# F103ZET6.net
KiCad netlist of a schematic drawn in Altium Designer
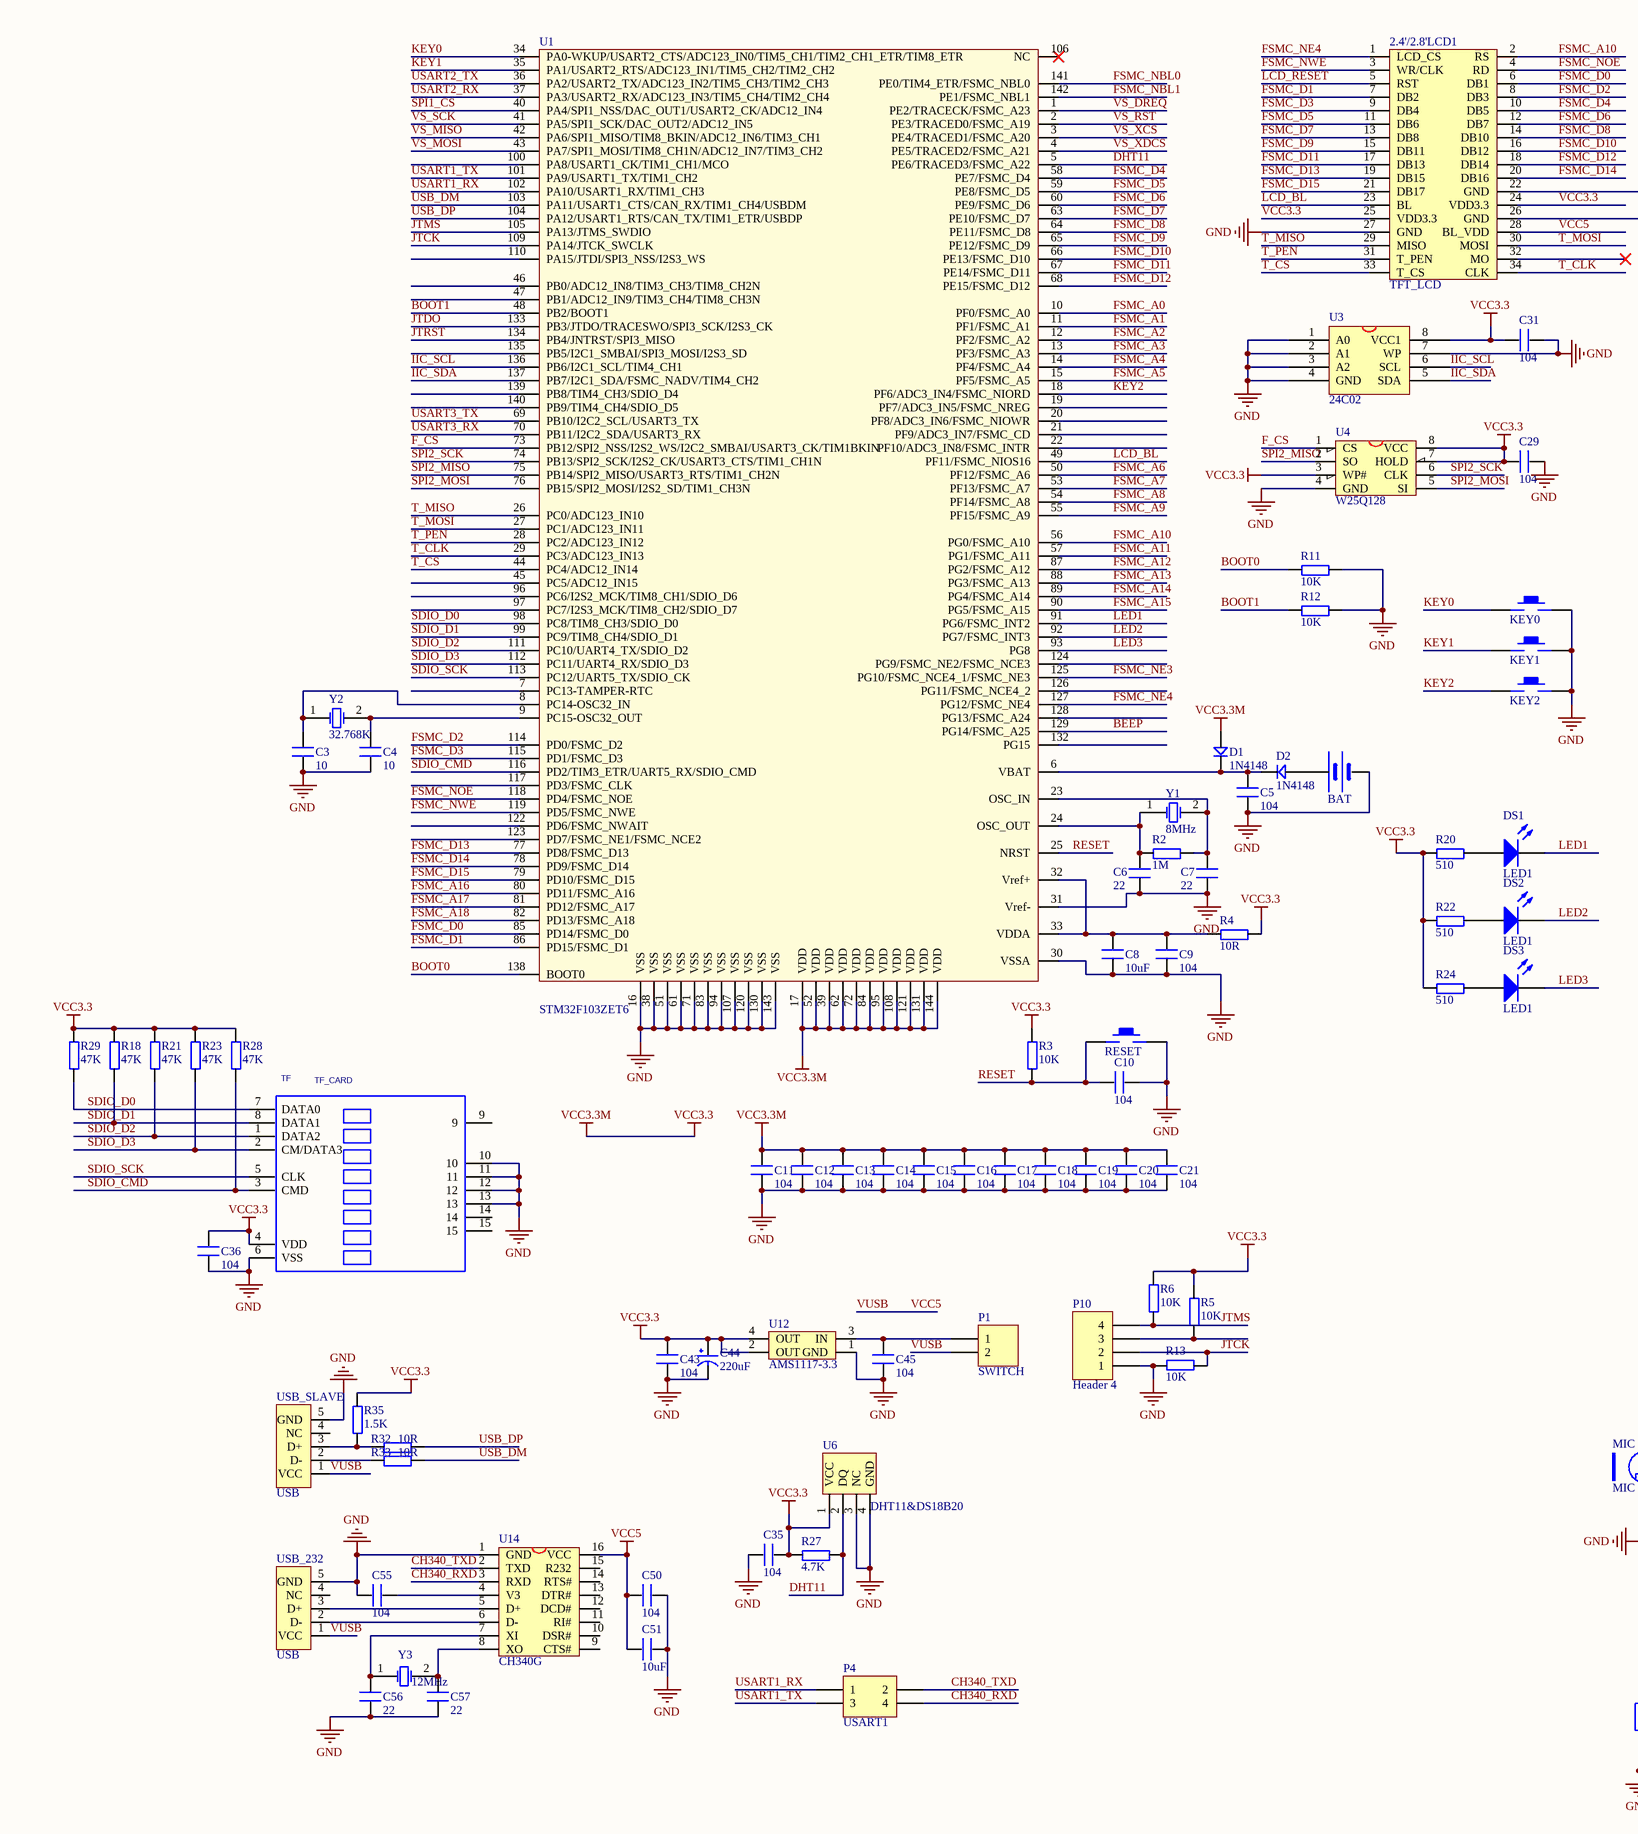
[diagram p0: F103ZET6.SchDoc, left]
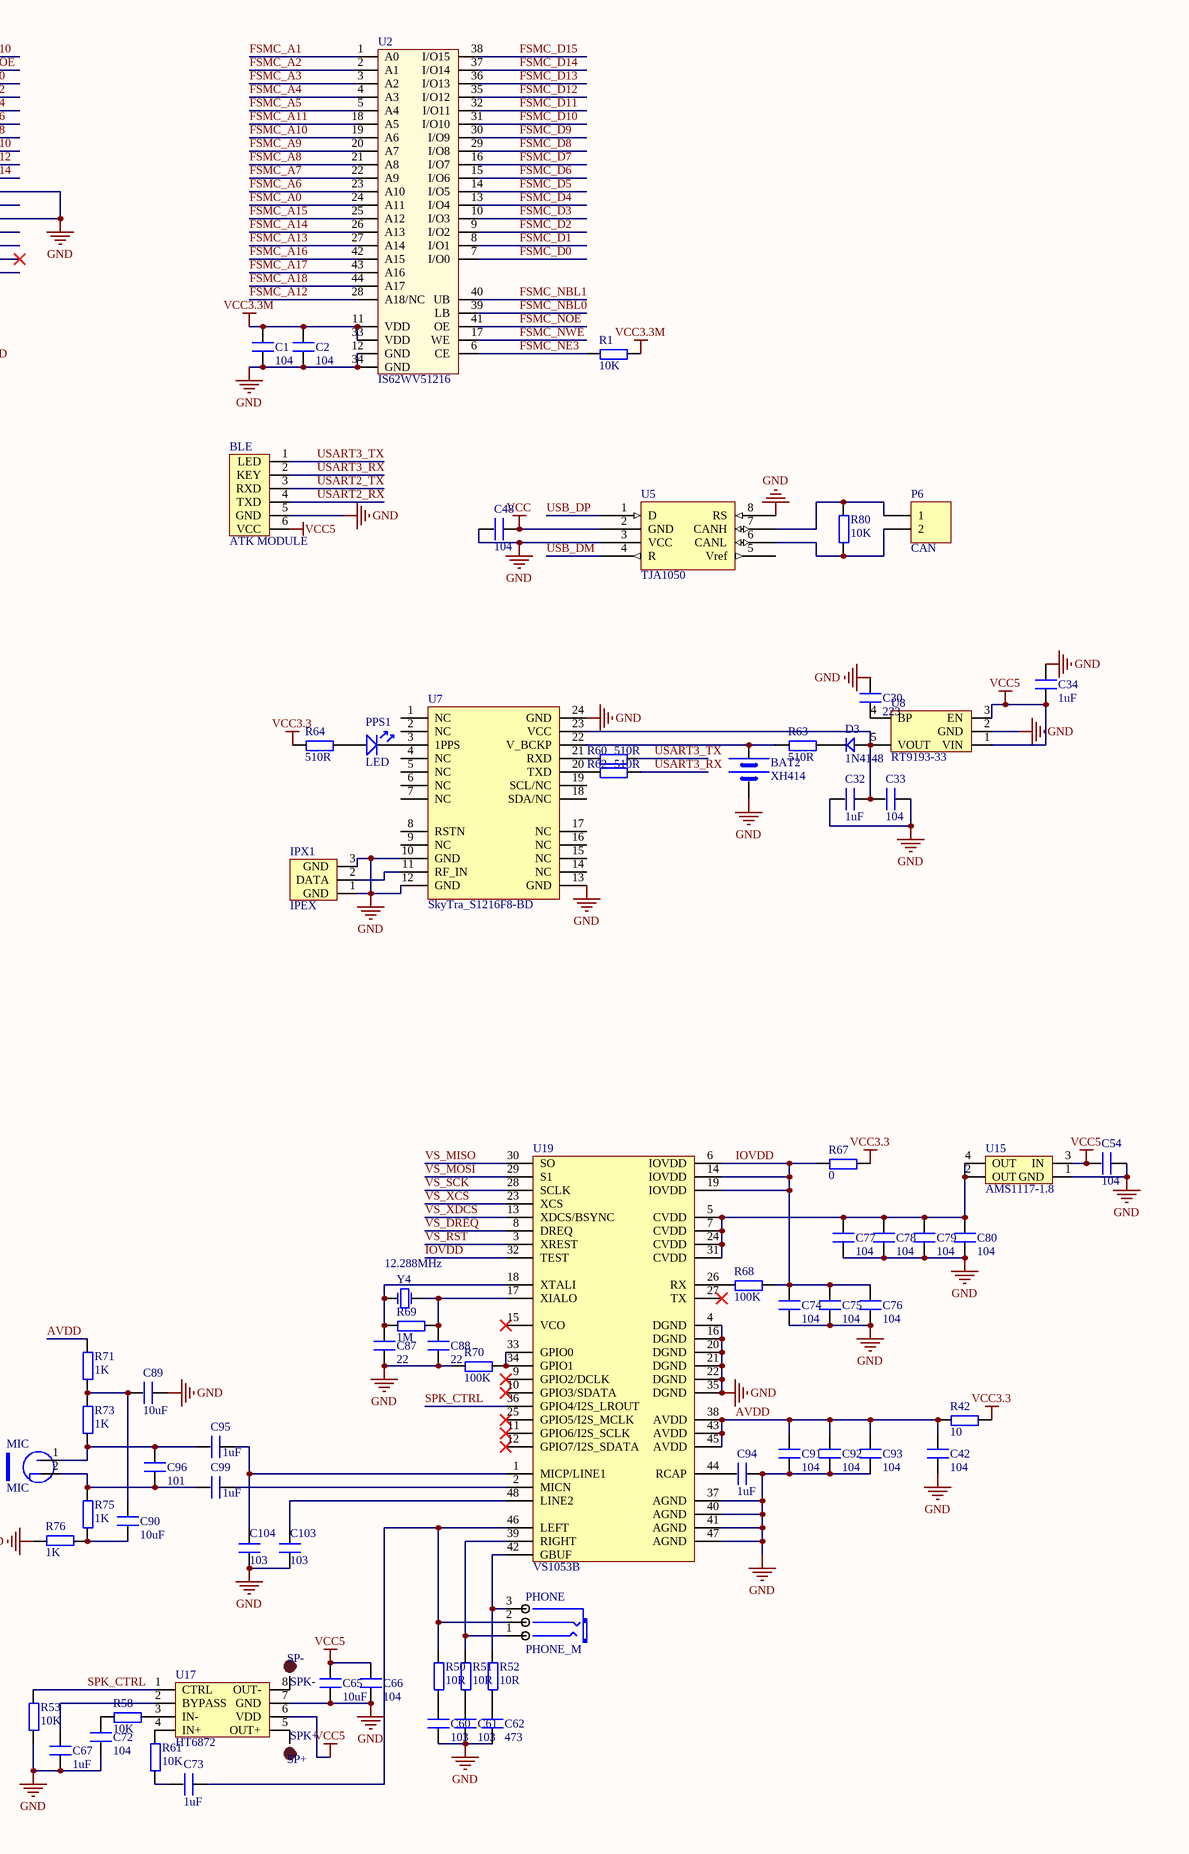
[diagram p1: F103ZET6.SchDoc, right]

(export (version "E")
  (design (tool "Eeschema 10.0.6"))
  (components
    (comp (ref "2.4'/2.8'LCD1")
      (value "TFT_LCD")
      (footprint "db2*17-4.3")
      (libsource (lib "WarShip V3 STM32103封装库") (part "TFT_LCD"))
    )
    (comp (ref "BAT")
      (value "BATT")
      (footprint "CR1220_A")
      (libsource (lib "WarShip V3 STM32103封装库") (part "BAT"))
    )
    (comp (ref "BAT2")
      (value "XH414")
      (footprint "XH414")
      (description "XH414 IV01E")
      (libsource (lib "ATK_S1216F8_BD_V1.1") (part "XH414"))
    )
    (comp (ref "BLE")
      (value "ATK MODULE")
      (footprint "HEAD6")
      (description "ATK-HC05")
      (libsource (lib "WarShip V3 STM32103封装库") (part "ATK-HC05"))
    )
    (comp (ref "C1")
      (value "104")
      (footprint "C 0603_M")
      (libsource (lib "WarShip V3 STM32103封装库") (part "C"))
    )
    (comp (ref "C2")
      (value "104")
      (footprint "C 0603_M")
      (libsource (lib "WarShip V3 STM32103封装库") (part "C"))
    )
    (comp (ref "C3")
      (value "10")
      (footprint "C 0603_M")
      (libsource (lib "WarShip V3 STM32103封装库") (part "C"))
    )
    (comp (ref "C4")
      (value "10")
      (footprint "C 0603_M")
      (libsource (lib "WarShip V3 STM32103封装库") (part "C"))
    )
    (comp (ref "C5")
      (value "104")
      (footprint "C 0603_M")
      (libsource (lib "WarShip V3 STM32103封装库") (part "C"))
    )
    (comp (ref "C6")
      (value "22")
      (footprint "C 0603_M")
      (libsource (lib "WarShip V3 STM32103封装库") (part "C"))
    )
    (comp (ref "C7")
      (value "22")
      (footprint "C 0603_M")
      (libsource (lib "WarShip V3 STM32103封装库") (part "C"))
    )
    (comp (ref "C8")
      (value "10uF")
      (footprint "C 0805_M")
      (libsource (lib "WarShip V3 STM32103封装库") (part "C"))
    )
    (comp (ref "C9")
      (value "104")
      (footprint "C 0603_M")
      (libsource (lib "WarShip V3 STM32103封装库") (part "C"))
    )
    (comp (ref "C10")
      (value "104")
      (footprint "C 0603_M")
      (libsource (lib "WarShip V3 STM32103封装库") (part "C"))
    )
    (comp (ref "C11")
      (value "104")
      (footprint "C 0603_M")
      (libsource (lib "WarShip V3 STM32103封装库") (part "C"))
    )
    (comp (ref "C12")
      (value "104")
      (footprint "C 0603_M")
      (libsource (lib "WarShip V3 STM32103封装库") (part "C"))
    )
    (comp (ref "C13")
      (value "104")
      (footprint "C 0603_M")
      (libsource (lib "WarShip V3 STM32103封装库") (part "C"))
    )
    (comp (ref "C14")
      (value "104")
      (footprint "C 0603_M")
      (libsource (lib "WarShip V3 STM32103封装库") (part "C"))
    )
    (comp (ref "C15")
      (value "104")
      (footprint "C 0603_M")
      (libsource (lib "WarShip V3 STM32103封装库") (part "C"))
    )
    (comp (ref "C16")
      (value "104")
      (footprint "C 0603_M")
      (libsource (lib "WarShip V3 STM32103封装库") (part "C"))
    )
    (comp (ref "C17")
      (value "104")
      (footprint "C 0603_M")
      (libsource (lib "WarShip V3 STM32103封装库") (part "C"))
    )
    (comp (ref "C18")
      (value "104")
      (footprint "C 0603_M")
      (libsource (lib "WarShip V3 STM32103封装库") (part "C"))
    )
    (comp (ref "C19")
      (value "104")
      (footprint "C 0603_M")
      (libsource (lib "WarShip V3 STM32103封装库") (part "C"))
    )
    (comp (ref "C20")
      (value "104")
      (footprint "C 0603_M")
      (libsource (lib "WarShip V3 STM32103封装库") (part "C"))
    )
    (comp (ref "C21")
      (value "104")
      (footprint "C 0603_M")
      (libsource (lib "WarShip V3 STM32103封装库") (part "C"))
    )
    (comp (ref "C29")
      (value "104")
      (footprint "C 0603_M")
      (libsource (lib "WarShip V3 STM32103封装库") (part "C"))
    )
    (comp (ref "C30") (value "223") (footprint "0603P") (libsource (lib "ATK_S1216F8_BD_V1.1") (part "C")))
    (comp (ref "C31")
      (value "104")
      (footprint "C 0603_M")
      (libsource (lib "WarShip V3 STM32103封装库") (part "C"))
    )
    (comp (ref "C32") (value "1uF") (footprint "0603P") (libsource (lib "ATK_S1216F8_BD_V1.1") (part "C")))
    (comp (ref "C33") (value "104") (footprint "0603P") (libsource (lib "ATK_S1216F8_BD_V1.1") (part "C")))
    (comp (ref "C34") (value "1uF") (footprint "0603P") (libsource (lib "ATK_S1216F8_BD_V1.1") (part "C")))
    (comp (ref "C35")
      (value "104")
      (footprint "C 0603_M")
      (libsource (lib "WarShip V3 STM32103封装库") (part "C"))
    )
    (comp (ref "C36")
      (value "104")
      (footprint "C 0603_M")
      (libsource (lib "WarShip V3 STM32103封装库") (part "C"))
    )
    (comp (ref "C42") (value "104") (footprint "C 0603_M") (libsource (lib "ATK-VS1053 MP3") (part "C")))
    (comp (ref "C43")
      (value "104")
      (footprint "C 0603_M")
      (libsource (lib "WarShip V3 STM32103封装库") (part "C"))
    )
    (comp (ref "C44")
      (value "220uF")
      (footprint "CT 6*6 - C")
      (libsource (lib "WarShip V3 STM32103封装库") (part "CAP"))
    )
    (comp (ref "C45")
      (value "104")
      (footprint "C 0603_M")
      (libsource (lib "WarShip V3 STM32103封装库") (part "C"))
    )
    (comp (ref "C48") (value "104") (footprint "0603P") (libsource (lib "WarShip V3 STM32103封装库") (part "C")))
    (comp (ref "C50")
      (value "104")
      (footprint "C 0603_M")
      (libsource (lib "WarShip V3 STM32103封装库") (part "C"))
    )
    (comp (ref "C51")
      (value "10uF")
      (footprint "C 0805_M")
      (libsource (lib "WarShip V3 STM32103封装库") (part "C"))
    )
    (comp (ref "C54") (value "104") (footprint "C 0603_M") (libsource (lib "ATK-VS1053 MP3") (part "C")))
    (comp (ref "C55")
      (value "104")
      (footprint "C 0603_M")
      (libsource (lib "WarShip V3 STM32103封装库") (part "C"))
    )
    (comp (ref "C56")
      (value "22")
      (footprint "C 0603_M")
      (libsource (lib "WarShip V3 STM32103封装库") (part "C"))
    )
    (comp (ref "C57")
      (value "22")
      (footprint "C 0603_M")
      (libsource (lib "WarShip V3 STM32103封装库") (part "C"))
    )
    (comp (ref "C60")
      (value "103")
      (footprint "C 0603_M")
      (libsource (lib "WarShip V3 STM32103封装库") (part "C"))
    )
    (comp (ref "C61")
      (value "103")
      (footprint "C 0603_M")
      (libsource (lib "WarShip V3 STM32103封装库") (part "C"))
    )
    (comp (ref "C62")
      (value "473")
      (footprint "C 0603_M")
      (libsource (lib "WarShip V3 STM32103封装库") (part "C"))
    )
    (comp (ref "C65")
      (value "10uF")
      (footprint "C 0805_M")
      (libsource (lib "WarShip V3 STM32103封装库") (part "C"))
    )
    (comp (ref "C66")
      (value "104")
      (footprint "C 0603_M")
      (libsource (lib "WarShip V3 STM32103封装库") (part "C"))
    )
    (comp (ref "C67")
      (value "1uF")
      (footprint "C 0603_M")
      (libsource (lib "WarShip V3 STM32103封装库") (part "C"))
    )
    (comp (ref "C72")
      (value "104")
      (footprint "C 0603_M")
      (libsource (lib "WarShip V3 STM32103封装库") (part "C"))
    )
    (comp (ref "C73")
      (value "1uF")
      (footprint "C 0603_M")
      (libsource (lib "WarShip V3 STM32103封装库") (part "C"))
    )
    (comp (ref "C74") (value "104") (footprint "C 0603_M") (libsource (lib "ATK-VS1053 MP3") (part "C")))
    (comp (ref "C75") (value "104") (footprint "C 0603_M") (libsource (lib "ATK-VS1053 MP3") (part "C")))
    (comp (ref "C76") (value "104") (footprint "C 0603_M") (libsource (lib "ATK-VS1053 MP3") (part "C")))
    (comp (ref "C77") (value "104") (footprint "C 0603_M") (libsource (lib "ATK-VS1053 MP3") (part "C")))
    (comp (ref "C78") (value "104") (footprint "C 0603_M") (libsource (lib "ATK-VS1053 MP3") (part "C")))
    (comp (ref "C79") (value "104") (footprint "C 0603_M") (libsource (lib "ATK-VS1053 MP3") (part "C")))
    (comp (ref "C80") (value "104") (footprint "C 0603_M") (libsource (lib "ATK-VS1053 MP3") (part "C")))
    (comp (ref "C87") (value "22") (footprint "C 0603_M") (libsource (lib "ATK-VS1053 MP3") (part "C")))
    (comp (ref "C88") (value "22") (footprint "C 0603_M") (libsource (lib "ATK-VS1053 MP3") (part "C")))
    (comp (ref "C89")
      (value "10uF")
      (footprint "C 0805_M")
      (libsource (lib "WarShip V3 STM32103封装库") (part "C"))
    )
    (comp (ref "C90")
      (value "10uF")
      (footprint "C 0805_M")
      (libsource (lib "WarShip V3 STM32103封装库") (part "C"))
    )
    (comp (ref "C91") (value "104") (footprint "C 0603_M") (libsource (lib "ATK-VS1053 MP3") (part "C")))
    (comp (ref "C92") (value "104") (footprint "C 0603_M") (libsource (lib "ATK-VS1053 MP3") (part "C")))
    (comp (ref "C93") (value "104") (footprint "C 0603_M") (libsource (lib "ATK-VS1053 MP3") (part "C")))
    (comp (ref "C94") (value "1uF") (footprint "C 0603_M") (libsource (lib "ATK-VS1053 MP3") (part "C")))
    (comp (ref "C95")
      (value "1uF")
      (footprint "C 0603_M")
      (libsource (lib "WarShip V3 STM32103封装库") (part "C"))
    )
    (comp (ref "C96")
      (value "101")
      (footprint "C 0603_M")
      (libsource (lib "WarShip V3 STM32103封装库") (part "C"))
    )
    (comp (ref "C99")
      (value "1uF")
      (footprint "C 0603_M")
      (libsource (lib "WarShip V3 STM32103封装库") (part "C"))
    )
    (comp (ref "C103")
      (value "103")
      (footprint "C 0603_M")
      (libsource (lib "WarShip V3 STM32103封装库") (part "C"))
    )
    (comp (ref "C104")
      (value "103")
      (footprint "C 0603_M")
      (libsource (lib "WarShip V3 STM32103封装库") (part "C"))
    )
    (comp (ref "D1")
      (value "1N4148")
      (footprint "DIODE_SOP")
      (libsource (lib "WarShip V3 STM32103封装库") (part "D"))
    )
    (comp (ref "D2")
      (value "1N4148")
      (footprint "DIODE_SOP")
      (libsource (lib "WarShip V3 STM32103封装库") (part "D"))
    )
    (comp (ref "D3")
      (value "1N4148")
      (footprint "DIODE_SOP")
      (libsource (lib "ATK_S1216F8_BD_V1.1") (part "D"))
    )
    (comp (ref "DS1")
      (value "LED1")
      (footprint "LED 0603R")
      (description "Typical RED, GREEN, YELLOW, AMBER GaAs LED")
      (fields (field (name "PUBLISHER") "Altium Limited"))
      (libsource (lib "WarShip V3 STM32103封装库") (part "LED2"))
    )
    (comp (ref "DS2")
      (value "LED1")
      (footprint "LED 0603R")
      (description "Typical RED, GREEN, YELLOW, AMBER GaAs LED")
      (fields (field (name "PUBLISHER") "Altium Limited"))
      (libsource (lib "WarShip V3 STM32103封装库") (part "LED2"))
    )
    (comp (ref "DS3")
      (value "LED1")
      (footprint "LED 0603R")
      (description "Typical RED, GREEN, YELLOW, AMBER GaAs LED")
      (fields (field (name "PUBLISHER") "Altium Limited"))
      (libsource (lib "WarShip V3 STM32103封装库") (part "LED2"))
    )
    (comp (ref "IPX1")
      (value "IPEX")
      (footprint "IPEX")
      (description "IPEX座")
      (libsource (lib "ATK_S1216F8_BD_V1.1") (part "IPEX"))
    )
    (comp (ref "KEY0")
      (value "KEY_M")
      (footprint "TSW SMD-3*6*2.5")
      (libsource (lib "WarShip V3 STM32103封装库") (part "KEY_M"))
    )
    (comp (ref "KEY1")
      (value "KEY_M")
      (footprint "TSW SMD-3*6*2.5")
      (libsource (lib "WarShip V3 STM32103封装库") (part "KEY_M"))
    )
    (comp (ref "KEY2")
      (value "KEY_M")
      (footprint "TSW SMD-3*6*2.5")
      (libsource (lib "WarShip V3 STM32103封装库") (part "KEY_M"))
    )
    (comp (ref "MIC") (value "MIC") (footprint "MIC") (libsource (lib "ATK-VS1053 MP3") (part "MIC")))
    (comp (ref "P1")
      (value "SWITCH")
      (footprint "HDR2.54-LI-2P")
      (description "Header, 2-Pin")
      (fields (field (name "PUBLISHER") "Altium Limited"))
      (libsource (lib "WarShip V3 STM32103封装库") (part "Header 2"))
    )
    (comp (ref "P4")
      (value "USART1")
      (footprint "HDR2.54-LI-2x2P")
      (description "Header, 2-Pin, Dual row")
      (fields (field (name "PUBLISHER") "Altium Limited"))
      (libsource (lib "WarShip V3 STM32103封装库") (part "Header 2X2"))
    )
    (comp (ref "P6")
      (value "CAN")
      (footprint "HDR1X2")
      (description "Header, 2-Pin")
      (fields (field (name "PUBLISHER") "Altium Limited"))
      (libsource (lib "WarShip V3 STM32103封装库") (part "Header 2"))
    )
    (comp (ref "P10")
      (value "Header 4")
      (footprint "HDR2.54-LI-4P")
      (description "Header, 4-Pin")
      (fields (field (name "PUBLISHER") "Altium Limited"))
      (libsource (lib "WarShip V3 STM32103封装库") (part "Header 4"))
    )
    (comp (ref "PHONE")
      (value "PHONE_M")
      (footprint "PHONE_ST")
      (libsource (lib "ATK-VS1053 MP3") (part "PHONE_M"))
    )
    (comp (ref "PPS1")
      (value "LED")
      (footprint "SMDLED")
      (libsource (lib "ATK_S1216F8_BD_V1.1") (part "LED"))
    )
    (comp (ref "R1")
      (value "10K")
      (footprint "R 0603_M")
      (libsource (lib "WarShip V3 STM32103封装库") (part "R"))
    )
    (comp (ref "R2")
      (value "1M")
      (footprint "R 0603_M")
      (libsource (lib "WarShip V3 STM32103封装库") (part "R"))
    )
    (comp (ref "R3")
      (value "10K")
      (footprint "R 0603_M")
      (libsource (lib "WarShip V3 STM32103封装库") (part "R"))
    )
    (comp (ref "R4")
      (value "10R")
      (footprint "R 0603_M")
      (libsource (lib "WarShip V3 STM32103封装库") (part "R"))
    )
    (comp (ref "R5")
      (value "10K")
      (footprint "R 0603_M")
      (libsource (lib "WarShip V3 STM32103封装库") (part "R"))
    )
    (comp (ref "R6")
      (value "10K")
      (footprint "R 0603_M")
      (libsource (lib "WarShip V3 STM32103封装库") (part "R"))
    )
    (comp (ref "R11")
      (value "10K")
      (footprint "R 0603_M")
      (libsource (lib "WarShip V3 STM32103封装库") (part "R"))
    )
    (comp (ref "R12")
      (value "10K")
      (footprint "R 0603_M")
      (libsource (lib "WarShip V3 STM32103封装库") (part "R"))
    )
    (comp (ref "R13")
      (value "10K")
      (footprint "R 0603_M")
      (libsource (lib "WarShip V3 STM32103封装库") (part "R"))
    )
    (comp (ref "R18")
      (value "47K")
      (footprint "R 0603_M")
      (libsource (lib "WarShip V3 STM32103封装库") (part "R"))
    )
    (comp (ref "R20") (value "510") (footprint "0603P") (libsource (lib "WarShip V3 STM32103封装库") (part "R")))
    (comp (ref "R21")
      (value "47K")
      (footprint "R 0603_M")
      (libsource (lib "WarShip V3 STM32103封装库") (part "R"))
    )
    (comp (ref "R22") (value "510") (footprint "0603P") (libsource (lib "WarShip V3 STM32103封装库") (part "R")))
    (comp (ref "R23")
      (value "47K")
      (footprint "R 0603_M")
      (libsource (lib "WarShip V3 STM32103封装库") (part "R"))
    )
    (comp (ref "R24") (value "510") (footprint "0603P") (libsource (lib "WarShip V3 STM32103封装库") (part "R")))
    (comp (ref "R27")
      (value "4.7K")
      (footprint "R 0603_M")
      (libsource (lib "WarShip V3 STM32103封装库") (part "R"))
    )
    (comp (ref "R28")
      (value "47K")
      (footprint "R 0603_M")
      (libsource (lib "WarShip V3 STM32103封装库") (part "R"))
    )
    (comp (ref "R29")
      (value "47K")
      (footprint "R 0603_M")
      (libsource (lib "WarShip V3 STM32103封装库") (part "R"))
    )
    (comp (ref "R32")
      (value "10R")
      (footprint "R 0603_M")
      (libsource (lib "WarShip V3 STM32103封装库") (part "R"))
    )
    (comp (ref "R33")
      (value "10R")
      (footprint "R 0603_M")
      (libsource (lib "WarShip V3 STM32103封装库") (part "R"))
    )
    (comp (ref "R35")
      (value "1.5K")
      (footprint "R 0603_M")
      (libsource (lib "WarShip V3 STM32103封装库") (part "R"))
    )
    (comp (ref "R42") (value "10") (footprint "R 0603_M") (libsource (lib "ATK-VS1053 MP3") (part "R")))
    (comp (ref "R50")
      (value "10R")
      (footprint "R 0603_M")
      (libsource (lib "WarShip V3 STM32103封装库") (part "R"))
    )
    (comp (ref "R51")
      (value "10R")
      (footprint "R 0603_M")
      (libsource (lib "WarShip V3 STM32103封装库") (part "R"))
    )
    (comp (ref "R52")
      (value "10R")
      (footprint "R 0603_M")
      (libsource (lib "WarShip V3 STM32103封装库") (part "R"))
    )
    (comp (ref "R53")
      (value "10K")
      (footprint "R 0603_M")
      (libsource (lib "WarShip V3 STM32103封装库") (part "R"))
    )
    (comp (ref "R58")
      (value "10K")
      (footprint "R 0603_M")
      (libsource (lib "WarShip V3 STM32103封装库") (part "R"))
    )
    (comp (ref "R60") (value "510R") (footprint "0603P") (libsource (lib "ATK_S1216F8_BD_V1.1") (part "R")))
    (comp (ref "R61")
      (value "10K")
      (footprint "R 0603_M")
      (libsource (lib "WarShip V3 STM32103封装库") (part "R"))
    )
    (comp (ref "R62") (value "510R") (footprint "0603P") (libsource (lib "ATK_S1216F8_BD_V1.1") (part "R")))
    (comp (ref "R63") (value "510R") (footprint "0603P") (libsource (lib "ATK_S1216F8_BD_V1.1") (part "R")))
    (comp (ref "R64") (value "510R") (footprint "0603P") (libsource (lib "ATK_S1216F8_BD_V1.1") (part "R")))
    (comp (ref "R67") (value "0") (footprint "R 0603_M") (libsource (lib "ATK-VS1053 MP3") (part "R")))
    (comp (ref "R68") (value "100K") (footprint "R 0603_M") (libsource (lib "ATK-VS1053 MP3") (part "R")))
    (comp (ref "R69") (value "1M") (footprint "R 0603_M") (libsource (lib "ATK-VS1053 MP3") (part "R")))
    (comp (ref "R70") (value "100K") (footprint "R 0603_M") (libsource (lib "ATK-VS1053 MP3") (part "R")))
    (comp (ref "R71")
      (value "1K")
      (footprint "R 0603_M")
      (libsource (lib "WarShip V3 STM32103封装库") (part "R"))
    )
    (comp (ref "R73")
      (value "1K")
      (footprint "R 0603_M")
      (libsource (lib "WarShip V3 STM32103封装库") (part "R"))
    )
    (comp (ref "R75")
      (value "1K")
      (footprint "R 0603_M")
      (libsource (lib "WarShip V3 STM32103封装库") (part "R"))
    )
    (comp (ref "R76")
      (value "1K")
      (footprint "R 0603_M")
      (libsource (lib "WarShip V3 STM32103封装库") (part "R"))
    )
    (comp (ref "R80") (value "10K") (footprint "0603P") (libsource (lib "WarShip V3 STM32103封装库") (part "R")))
    (comp (ref "RESET")
      (value "KEY_M")
      (footprint "TSW SMD-3*6*2.5")
      (libsource (lib "WarShip V3 STM32103封装库") (part "KEY_M"))
    )
    (comp (ref "SP+")
      (value "SPK+")
      (footprint "TP-1.5")
      (description "测试点")
      (libsource (lib "WarShip V3 STM32103封装库") (part "TEST-POINT"))
    )
    (comp (ref "SP-")
      (value "SPK-")
      (footprint "TP-1.5")
      (description "测试点")
      (libsource (lib "WarShip V3 STM32103封装库") (part "TEST-POINT"))
    )
    (comp (ref "TF") (value "TF_CARD") (footprint "TF_CARD") (libsource (lib "ISO-V3") (part "TF_CARD")))
    (comp (ref "U1")
      (value "STM32F103ZET6")
      (footprint "LQFP144")
      (libsource (lib "WarShip V3 STM32103封装库") (part "STM32F103ZET6"))
    )
    (comp (ref "U2")
      (value "IS62WV51216")
      (footprint "TSOP44")
      (libsource (lib "WarShip V3 STM32103封装库") (part "IS61LV51216"))
    )
    (comp (ref "U3")
      (value "24C02")
      (footprint "SOP-8")
      (libsource (lib "WarShip V3 STM32103封装库") (part "24C256"))
    )
    (comp (ref "U4")
      (value "W25Q128")
      (footprint "SOIC-8")
      (description "W25X16;SST25VF016;MX25L1605")
      (libsource (lib "WarShip V3 STM32103封装库") (part "W25X16"))
    )
    (comp (ref "U5")
      (value "TJA1050")
      (footprint "SOP-8")
      (libsource (lib "WarShip V3 STM32103封装库") (part "SN65HVD230D"))
    )
    (comp (ref "U6")
      (value "DHT11&DS18B20")
      (footprint "DHT11")
      (description "数字温湿度传感器")
      (libsource (lib "WarShip V3 STM32103封装库") (part "DHT11"))
    )
    (comp (ref "U7")
      (value "SkyTra_S1216F8-BD")
      (footprint "GPS_NEO-6")
      (libsource (lib "ATK_S1216F8_BD_V1.1") (part "SkyTra_GPS"))
    )
    (comp (ref "U8")
      (value "RT9193-33")
      (footprint "SOT-23-5")
      (description "3.3V超低压差LDO")
      (libsource (lib "ATK_S1216F8_BD_V1.1") (part "RT9193-33"))
    )
    (comp (ref "U12")
      (value "AMS1117-3.3")
      (footprint "AMS1117")
      (libsource (lib "WarShip V3 STM32103封装库") (part "AMS1117"))
    )
    (comp (ref "U14")
      (value "CH340G")
      (footprint "SOP16M")
      (description "USB2UART")
      (libsource (lib "WarShip V3 STM32103封装库") (part "CH340G"))
    )
    (comp (ref "U15")
      (value "AMS1117-1.8")
      (footprint "AMS1117")
      (libsource (lib "ATK-VS1053 MP3") (part "AMS1117"))
    )
    (comp (ref "U17")
      (value "HT6872")
      (footprint "SOP-8")
      (description "HT6871")
      (libsource (lib "WarShip V3 STM32103封装库") (part "HT6871"))
    )
    (comp (ref "U19")
      (value "VS1053B")
      (footprint "mTQFP48")
      (libsource (lib "ATK-VS1053 MP3") (part "VS1053"))
    )
    (comp (ref "USB_232")
      (value "USB")
      (footprint "USB-MINI-A")
      (libsource (lib "WarShip V3 STM32103封装库") (part "USB5"))
    )
    (comp (ref "USB_SLAVE")
      (value "USB")
      (footprint "USB-MINI-A")
      (libsource (lib "WarShip V3 STM32103封装库") (part "USB5"))
    )
    (comp (ref "Y1")
      (value "8MHz")
      (footprint "OSC HC-49S")
      (description "Crystal Oscillator")
      (fields (field (name "PUBLISHER") "Altium Limited"))
      (libsource (lib "WarShip V3 STM32103封装库") (part "XTAL"))
    )
    (comp (ref "Y2")
      (value "32.768K")
      (footprint "OSC-2x6-WI-A")
      (description "Crystal Oscillator")
      (fields (field (name "PUBLISHER") "Altium Limited"))
      (libsource (lib "WarShip V3 STM32103封装库") (part "XTAL"))
    )
    (comp (ref "Y3")
      (value "12MHz")
      (footprint "OSC HC-49S")
      (description "Crystal Oscillator")
      (fields (field (name "PUBLISHER") "Altium Limited"))
      (libsource (lib "WarShip V3 STM32103封装库") (part "XTAL"))
    )
    (comp (ref "Y4")
      (value "12.288MHz")
      (footprint "OSC HC-49S")
      (description "Crystal Oscillator")
      (fields (field (name "PUBLISHER") "Altium Limited"))
      (libsource (lib "ATK-VS1053 MP3") (part "XTAL"))
    )
  )
  (nets
    (net (code "1") (name "/AVDD") (class "Default")
      (node (ref "C42") (pin "2") (pintype "passive"))
      (node (ref "C91") (pin "2") (pintype "passive"))
      (node (ref "C92") (pin "2") (pintype "passive"))
      (node (ref "C93") (pin "2") (pintype "passive"))
      (node (ref "R42") (pin "1") (pintype "passive"))
      (node (ref "R71") (pin "2") (pintype "passive"))
      (node (ref "U19") (pin "38") (pinfunction "AVDD_38") (pintype "passive"))
      (node (ref "U19") (pin "43") (pinfunction "AVDD_43") (pintype "passive"))
      (node (ref "U19") (pin "45") (pinfunction "AVDD_45") (pintype "passive"))
    )
    (net (code "2") (name "/BEEP") (class "Default")
      (node (ref "U1") (pin "129") (pinfunction "PG14/FSMC_A25_129") (pintype "passive"))
    )
    (net (code "3") (name "/BOOT0") (class "Default")
      (node (ref "R11") (pin "1") (pintype "passive"))
      (node (ref "U1") (pin "138") (pinfunction "BOOT0_138") (pintype "passive"))
    )
    (net (code "4") (name "/BOOT1") (class "Default")
      (node (ref "R12") (pin "1") (pintype "passive"))
      (node (ref "U1") (pin "48") (pinfunction "PB2/BOOT1_48") (pintype "passive"))
    )
    (net (code "5") (name "/CH340_RXD") (class "Default")
      (node (ref "P4") (pin "4") (pinfunction "4_4") (pintype "passive"))
      (node (ref "U14") (pin "3") (pinfunction "RXD_3") (pintype "passive"))
    )
    (net (code "6") (name "/CH340_TXD") (class "Default")
      (node (ref "P4") (pin "2") (pinfunction "2_2") (pintype "passive"))
      (node (ref "U14") (pin "2") (pinfunction "TXD_2") (pintype "passive"))
    )
    (net (code "7") (name "/DHT11") (class "Default")
      (node (ref "R27") (pin "2") (pintype "passive"))
      (node (ref "U1") (pin "5") (pinfunction "PE6/TRACED3/FSMC_A22_5") (pintype "passive"))
      (node (ref "U6") (pin "2") (pinfunction "DQ_2") (pintype "passive"))
    )
    (net (code "8") (name "/FSMC_A0") (class "Default")
      (node (ref "U1") (pin "10") (pinfunction "PF0/FSMC_A0_10") (pintype "passive"))
      (node (ref "U2") (pin "24") (pinfunction "A11_24") (pintype "passive"))
    )
    (net (code "9") (name "/FSMC_A1") (class "Default")
      (node (ref "U1") (pin "11") (pinfunction "PF1/FSMC_A1_11") (pintype "passive"))
      (node (ref "U2") (pin "1") (pinfunction "A0_1") (pintype "passive"))
    )
    (net (code "10") (name "/FSMC_A2") (class "Default")
      (node (ref "U1") (pin "12") (pinfunction "PF2/FSMC_A2_12") (pintype "passive"))
      (node (ref "U2") (pin "2") (pinfunction "A1_2") (pintype "passive"))
    )
    (net (code "11") (name "/FSMC_A3") (class "Default")
      (node (ref "U1") (pin "13") (pinfunction "PF3/FSMC_A3_13") (pintype "passive"))
      (node (ref "U2") (pin "3") (pinfunction "A2_3") (pintype "passive"))
    )
    (net (code "12") (name "/FSMC_A4") (class "Default")
      (node (ref "U1") (pin "14") (pinfunction "PF4/FSMC_A4_14") (pintype "passive"))
      (node (ref "U2") (pin "4") (pinfunction "A3_4") (pintype "passive"))
    )
    (net (code "13") (name "/FSMC_A5") (class "Default")
      (node (ref "U1") (pin "15") (pinfunction "PF5/FSMC_A5_15") (pintype "passive"))
      (node (ref "U2") (pin "5") (pinfunction "A4_5") (pintype "passive"))
    )
    (net (code "14") (name "/FSMC_A6") (class "Default")
      (node (ref "U1") (pin "50") (pinfunction "PF12/FSMC_A6_50") (pintype "passive"))
      (node (ref "U2") (pin "23") (pinfunction "A10_23") (pintype "passive"))
    )
    (net (code "15") (name "/FSMC_A7") (class "Default")
      (node (ref "U1") (pin "53") (pinfunction "PF13/FSMC_A7_53") (pintype "passive"))
      (node (ref "U2") (pin "22") (pinfunction "A9_22") (pintype "passive"))
    )
    (net (code "16") (name "/FSMC_A8") (class "Default")
      (node (ref "U1") (pin "54") (pinfunction "PF14/FSMC_A8_54") (pintype "passive"))
      (node (ref "U2") (pin "21") (pinfunction "A8_21") (pintype "passive"))
    )
    (net (code "17") (name "/FSMC_A9") (class "Default")
      (node (ref "U1") (pin "55") (pinfunction "PF15/FSMC_A9_55") (pintype "passive"))
      (node (ref "U2") (pin "20") (pinfunction "A7_20") (pintype "passive"))
    )
    (net (code "18") (name "/FSMC_A10") (class "Default")
      (node (ref "2.4'/2.8'LCD1") (pin "2") (pinfunction "RS_2") (pintype "passive"))
      (node (ref "U1") (pin "56") (pinfunction "PG0/FSMC_A10_56") (pintype "passive"))
      (node (ref "U2") (pin "19") (pinfunction "A6_19") (pintype "passive"))
    )
    (net (code "19") (name "/FSMC_A11") (class "Default")
      (node (ref "U1") (pin "57") (pinfunction "PG1/FSMC_A11_57") (pintype "passive"))
      (node (ref "U2") (pin "18") (pinfunction "A5_18") (pintype "passive"))
    )
    (net (code "20") (name "/FSMC_A12") (class "Default")
      (node (ref "U1") (pin "87") (pinfunction "PG2/FSMC_A12_87") (pintype "passive"))
      (node (ref "U2") (pin "28") (pinfunction "A18/NC_28") (pintype "passive"))
    )
    (net (code "21") (name "/FSMC_A13") (class "Default")
      (node (ref "U1") (pin "88") (pinfunction "PG3/FSMC_A13_88") (pintype "passive"))
      (node (ref "U2") (pin "27") (pinfunction "A14_27") (pintype "passive"))
    )
    (net (code "22") (name "/FSMC_A14") (class "Default")
      (node (ref "U1") (pin "89") (pinfunction "PG4/FSMC_A14_89") (pintype "passive"))
      (node (ref "U2") (pin "26") (pinfunction "A13_26") (pintype "passive"))
    )
    (net (code "23") (name "/FSMC_A15") (class "Default")
      (node (ref "U1") (pin "90") (pinfunction "PG5/FSMC_A15_90") (pintype "passive"))
      (node (ref "U2") (pin "25") (pinfunction "A12_25") (pintype "passive"))
    )
    (net (code "24") (name "/FSMC_A16") (class "Default")
      (node (ref "U1") (pin "80") (pinfunction "PD11/FSMC_A16_80") (pintype "passive"))
      (node (ref "U2") (pin "42") (pinfunction "A15_42") (pintype "passive"))
    )
    (net (code "25") (name "/FSMC_A17") (class "Default")
      (node (ref "U1") (pin "81") (pinfunction "PD12/FSMC_A17_81") (pintype "passive"))
      (node (ref "U2") (pin "43") (pinfunction "A16_43") (pintype "passive"))
    )
    (net (code "26") (name "/FSMC_A18") (class "Default")
      (node (ref "U1") (pin "82") (pinfunction "PD13/FSMC_A18_82") (pintype "passive"))
      (node (ref "U2") (pin "44") (pinfunction "A17_44") (pintype "passive"))
    )
    (net (code "27") (name "/FSMC_D0") (class "Default")
      (node (ref "2.4'/2.8'LCD1") (pin "6") (pinfunction "DB1_6") (pintype "passive"))
      (node (ref "U1") (pin "85") (pinfunction "PD14/FSMC_D0_85") (pintype "passive"))
      (node (ref "U2") (pin "7") (pinfunction "I/O0_7") (pintype "passive"))
    )
    (net (code "28") (name "/FSMC_D1") (class "Default")
      (node (ref "2.4'/2.8'LCD1") (pin "7") (pinfunction "DB2_7") (pintype "passive"))
      (node (ref "U1") (pin "86") (pinfunction "PD15/FSMC_D1_86") (pintype "passive"))
      (node (ref "U2") (pin "8") (pinfunction "I/O1_8") (pintype "passive"))
    )
    (net (code "29") (name "/FSMC_D2") (class "Default")
      (node (ref "2.4'/2.8'LCD1") (pin "8") (pinfunction "DB3_8") (pintype "passive"))
      (node (ref "U1") (pin "114") (pinfunction "PD0/FSMC_D2_114") (pintype "passive"))
      (node (ref "U2") (pin "9") (pinfunction "I/O2_9") (pintype "passive"))
    )
    (net (code "30") (name "/FSMC_D3") (class "Default")
      (node (ref "2.4'/2.8'LCD1") (pin "9") (pinfunction "DB4_9") (pintype "passive"))
      (node (ref "U1") (pin "115") (pinfunction "PD1/FSMC_D3_115") (pintype "passive"))
      (node (ref "U2") (pin "10") (pinfunction "I/O3_10") (pintype "passive"))
    )
    (net (code "31") (name "/FSMC_D4") (class "Default")
      (node (ref "2.4'/2.8'LCD1") (pin "10") (pinfunction "DB5_10") (pintype "passive"))
      (node (ref "U1") (pin "58") (pinfunction "PE7/FSMC_D4_58") (pintype "passive"))
      (node (ref "U2") (pin "13") (pinfunction "I/O4_13") (pintype "passive"))
    )
    (net (code "32") (name "/FSMC_D5") (class "Default")
      (node (ref "2.4'/2.8'LCD1") (pin "11") (pinfunction "DB6_11") (pintype "passive"))
      (node (ref "U1") (pin "59") (pinfunction "PE8/FSMC_D5_59") (pintype "passive"))
      (node (ref "U2") (pin "14") (pinfunction "I/O5_14") (pintype "passive"))
    )
    (net (code "33") (name "/FSMC_D6") (class "Default")
      (node (ref "2.4'/2.8'LCD1") (pin "12") (pinfunction "DB7_12") (pintype "passive"))
      (node (ref "U1") (pin "60") (pinfunction "PE9/FSMC_D6_60") (pintype "passive"))
      (node (ref "U2") (pin "15") (pinfunction "I/O6_15") (pintype "passive"))
    )
    (net (code "34") (name "/FSMC_D7") (class "Default")
      (node (ref "2.4'/2.8'LCD1") (pin "13") (pinfunction "DB8_13") (pintype "passive"))
      (node (ref "U1") (pin "63") (pinfunction "PE10/FSMC_D7_63") (pintype "passive"))
      (node (ref "U2") (pin "16") (pinfunction "I/O7_16") (pintype "passive"))
    )
    (net (code "35") (name "/FSMC_D8") (class "Default")
      (node (ref "2.4'/2.8'LCD1") (pin "14") (pinfunction "DB10_14") (pintype "passive"))
      (node (ref "U1") (pin "64") (pinfunction "PE11/FSMC_D8_64") (pintype "passive"))
      (node (ref "U2") (pin "29") (pinfunction "I/O8_29") (pintype "passive"))
    )
    (net (code "36") (name "/FSMC_D9") (class "Default")
      (node (ref "2.4'/2.8'LCD1") (pin "15") (pinfunction "DB11_15") (pintype "passive"))
      (node (ref "U1") (pin "65") (pinfunction "PE12/FSMC_D9_65") (pintype "passive"))
      (node (ref "U2") (pin "30") (pinfunction "I/O9_30") (pintype "passive"))
    )
    (net (code "37") (name "/FSMC_D10") (class "Default")
      (node (ref "2.4'/2.8'LCD1") (pin "16") (pinfunction "DB12_16") (pintype "passive"))
      (node (ref "U1") (pin "66") (pinfunction "PE13/FSMC_D10_66") (pintype "passive"))
      (node (ref "U2") (pin "31") (pinfunction "I/O10_31") (pintype "passive"))
    )
    (net (code "38") (name "/FSMC_D11") (class "Default")
      (node (ref "2.4'/2.8'LCD1") (pin "17") (pinfunction "DB13_17") (pintype "passive"))
      (node (ref "U1") (pin "67") (pinfunction "PE14/FSMC_D11_67") (pintype "passive"))
      (node (ref "U2") (pin "32") (pinfunction "I/O11_32") (pintype "passive"))
    )
    (net (code "39") (name "/FSMC_D12") (class "Default")
      (node (ref "2.4'/2.8'LCD1") (pin "18") (pinfunction "DB14_18") (pintype "passive"))
      (node (ref "U1") (pin "68") (pinfunction "PE15/FSMC_D12_68") (pintype "passive"))
      (node (ref "U2") (pin "35") (pinfunction "I/O12_35") (pintype "passive"))
    )
    (net (code "40") (name "/FSMC_D13") (class "Default")
      (node (ref "2.4'/2.8'LCD1") (pin "19") (pinfunction "DB15_19") (pintype "passive"))
      (node (ref "U1") (pin "77") (pinfunction "PD8/FSMC_D13_77") (pintype "passive"))
      (node (ref "U2") (pin "36") (pinfunction "I/O13_36") (pintype "passive"))
    )
    (net (code "41") (name "/FSMC_D14") (class "Default")
      (node (ref "2.4'/2.8'LCD1") (pin "20") (pinfunction "DB16_20") (pintype "passive"))
      (node (ref "U1") (pin "78") (pinfunction "PD9/FSMC_D14_78") (pintype "passive"))
      (node (ref "U2") (pin "37") (pinfunction "I/O14_37") (pintype "passive"))
    )
    (net (code "42") (name "/FSMC_D15") (class "Default")
      (node (ref "2.4'/2.8'LCD1") (pin "21") (pinfunction "DB17_21") (pintype "passive"))
      (node (ref "U1") (pin "79") (pinfunction "PD10/FSMC_D15_79") (pintype "passive"))
      (node (ref "U2") (pin "38") (pinfunction "I/O15_38") (pintype "passive"))
    )
    (net (code "43") (name "/FSMC_NBL0") (class "Default")
      (node (ref "U1") (pin "141") (pinfunction "PE0/TIM4_ETR/FSMC_NBL0_141") (pintype "passive"))
      (node (ref "U2") (pin "39") (pinfunction "LB_39") (pintype "passive"))
    )
    (net (code "44") (name "/FSMC_NBL1") (class "Default")
      (node (ref "U1") (pin "142") (pinfunction "PE1/FSMC_NBL1_142") (pintype "passive"))
      (node (ref "U2") (pin "40") (pinfunction "UB_40") (pintype "passive"))
    )
    (net (code "45") (name "/FSMC_NE3") (class "Default")
      (node (ref "R1") (pin "1") (pintype "passive"))
      (node (ref "U1") (pin "125") (pinfunction "PG10/FSMC_NCE4_1/FSMC_NE3_125") (pintype "passive"))
      (node (ref "U2") (pin "6") (pinfunction "CE_6") (pintype "passive"))
    )
    (net (code "46") (name "/FSMC_NE4") (class "Default")
      (node (ref "2.4'/2.8'LCD1") (pin "1") (pinfunction "LCD_CS_1") (pintype "passive"))
      (node (ref "U1") (pin "127") (pinfunction "PG12/FSMC_NE4_127") (pintype "passive"))
    )
    (net (code "47") (name "/FSMC_NOE") (class "Default")
      (node (ref "2.4'/2.8'LCD1") (pin "4") (pinfunction "RD_4") (pintype "passive"))
      (node (ref "U1") (pin "118") (pinfunction "PD4/FSMC_NOE_118") (pintype "passive"))
      (node (ref "U2") (pin "41") (pinfunction "OE_41") (pintype "passive"))
    )
    (net (code "48") (name "/FSMC_NWE") (class "Default")
      (node (ref "2.4'/2.8'LCD1") (pin "3") (pinfunction "WR/CLK_3") (pintype "passive"))
      (node (ref "U1") (pin "119") (pinfunction "PD5/FSMC_NWE_119") (pintype "passive"))
      (node (ref "U2") (pin "17") (pinfunction "WE_17") (pintype "passive"))
    )
    (net (code "49") (name "/F_CS") (class "Default")
      (node (ref "U1") (pin "73") (pinfunction "PB12/SPI2_NSS/I2S2_WS/I2C2_SMBAI/USART3_CK/TIM1BKIN_73") (pintype "passive"))
      (node (ref "U4") (pin "1") (pinfunction "CS_1") (pintype "passive"))
    )
    (net (code "50") (name "/IIC_SCL") (class "Default")
      (node (ref "U1") (pin "136") (pinfunction "PB6/I2C1_SCL/TIM4_CH1_136") (pintype "passive"))
      (node (ref "U3") (pin "6") (pinfunction "SCL_6") (pintype "passive"))
    )
    (net (code "51") (name "/IIC_SDA") (class "Default")
      (node (ref "U1") (pin "137") (pinfunction "PB7/I2C1_SDA/FSMC_NADV/TIM4_CH2_137") (pintype "passive"))
      (node (ref "U3") (pin "5") (pinfunction "SDA_5") (pintype "passive"))
    )
    (net (code "52") (name "/IOVDD") (class "Default")
      (node (ref "C74") (pin "2") (pintype "passive"))
      (node (ref "C75") (pin "2") (pintype "passive"))
      (node (ref "C76") (pin "2") (pintype "passive"))
      (node (ref "R67") (pin "1") (pintype "passive"))
      (node (ref "R68") (pin "2") (pintype "passive"))
      (node (ref "U19") (pin "14") (pinfunction "IOVDD_14") (pintype "passive"))
      (node (ref "U19") (pin "19") (pinfunction "IOVDD_19") (pintype "passive"))
      (node (ref "U19") (pin "32") (pinfunction "TEST_32") (pintype "passive"))
      (node (ref "U19") (pin "6") (pinfunction "IOVDD_6") (pintype "passive"))
    )
    (net (code "53") (name "/JTCK") (class "Default")
      (node (ref "P10") (pin "2") (pinfunction "2_2") (pintype "passive"))
      (node (ref "R13") (pin "1") (pintype "passive"))
      (node (ref "U1") (pin "109") (pinfunction "PA14/JTCK_SWCLK_109") (pintype "passive"))
    )
    (net (code "54") (name "/JTDO") (class "Default")
      (node (ref "U1") (pin "133") (pinfunction "PB3/JTDO/TRACESWO/SPI3_SCK/I2S3_CK_133") (pintype "passive"))
    )
    (net (code "55") (name "/JTMS") (class "Default")
      (node (ref "P10") (pin "4") (pinfunction "4_4") (pintype "passive"))
      (node (ref "R6") (pin "1") (pintype "passive"))
      (node (ref "U1") (pin "105") (pinfunction "PA13/JTMS_SWDIO_105") (pintype "passive"))
    )
    (net (code "56") (name "/JTRST") (class "Default")
      (node (ref "U1") (pin "134") (pinfunction "PB4/JNTRST/SPI3_MISO_134") (pintype "passive"))
    )
    (net (code "57") (name "/KEY0") (class "Default")
      (node (ref "KEY0") (pin "1") (pinfunction "1_1") (pintype "passive"))
      (node (ref "U1") (pin "34") (pinfunction "PA0-WKUP/USART2_CTS/ADC123_IN0/TIM5_CH1/TIM2_CH1_ETR/TIM8_ETR_34") (pintype "passive"))
    )
    (net (code "58") (name "/KEY1") (class "Default")
      (node (ref "KEY1") (pin "1") (pinfunction "1_1") (pintype "passive"))
      (node (ref "U1") (pin "35") (pinfunction "PA1/USART2_RTS/ADC123_IN1/TIM5_CH2/TIM2_CH2_35") (pintype "passive"))
    )
    (net (code "59") (name "/KEY2") (class "Default")
      (node (ref "KEY2") (pin "1") (pinfunction "1_1") (pintype "passive"))
      (node (ref "U1") (pin "18") (pinfunction "PF6/ADC3_IN4/FSMC_NIORD_18") (pintype "passive"))
    )
    (net (code "60") (name "/LCD_BL") (class "Default")
      (node (ref "2.4'/2.8'LCD1") (pin "23") (pinfunction "BL_23") (pintype "passive"))
      (node (ref "U1") (pin "49") (pinfunction "PF11/FSMC_NIOS16_49") (pintype "passive"))
    )
    (net (code "61") (name "/LCD_RESET") (class "Default")
      (node (ref "2.4'/2.8'LCD1") (pin "5") (pinfunction "RST_5") (pintype "passive"))
    )
    (net (code "62") (name "/LED1") (class "Default")
      (node (ref "DS1") (pin "2") (pinfunction "K_2") (pintype "passive"))
      (node (ref "U1") (pin "91") (pinfunction "PG6/FSMC_INT2_91") (pintype "passive"))
    )
    (net (code "63") (name "/LED2") (class "Default")
      (node (ref "DS2") (pin "2") (pinfunction "K_2") (pintype "passive"))
      (node (ref "U1") (pin "92") (pinfunction "PG7/FSMC_INT3_92") (pintype "passive"))
    )
    (net (code "64") (name "/LED3") (class "Default")
      (node (ref "DS3") (pin "2") (pinfunction "K_2") (pintype "passive"))
      (node (ref "U1") (pin "93") (pinfunction "PG8_93") (pintype "passive"))
    )
    (net (code "65") (name "/RESET") (class "Default")
      (node (ref "C10") (pin "2") (pintype "passive"))
      (node (ref "R3") (pin "1") (pintype "passive"))
      (node (ref "RESET") (pin "1") (pinfunction "1_1") (pintype "passive"))
      (node (ref "U1") (pin "25") (pinfunction "NRST_25") (pintype "passive"))
    )
    (net (code "66") (name "/SDIO_CMD") (class "Default")
      (node (ref "R28") (pin "1") (pintype "passive"))
      (node (ref "TF") (pin "3") (pinfunction "CMD_3") (pintype "passive"))
      (node (ref "U1") (pin "116") (pinfunction "PD2/TIM3_ETR/UART5_RX/SDIO_CMD_116") (pintype "passive"))
    )
    (net (code "67") (name "/SDIO_D0") (class "Default")
      (node (ref "R29") (pin "1") (pintype "passive"))
      (node (ref "TF") (pin "7") (pinfunction "DATA0_7") (pintype "passive"))
      (node (ref "U1") (pin "98") (pinfunction "PC8/TIM8_CH3/SDIO_D0_98") (pintype "passive"))
    )
    (net (code "68") (name "/SDIO_D1") (class "Default")
      (node (ref "R18") (pin "1") (pintype "passive"))
      (node (ref "TF") (pin "8") (pinfunction "DATA1_8") (pintype "passive"))
      (node (ref "U1") (pin "99") (pinfunction "PC9/TIM8_CH4/SDIO_D1_99") (pintype "passive"))
    )
    (net (code "69") (name "/SDIO_D2") (class "Default")
      (node (ref "R21") (pin "1") (pintype "passive"))
      (node (ref "TF") (pin "1") (pinfunction "DATA2_1") (pintype "passive"))
      (node (ref "U1") (pin "111") (pinfunction "PC10/UART4_TX/SDIO_D2_111") (pintype "passive"))
    )
    (net (code "70") (name "/SDIO_D3") (class "Default")
      (node (ref "R23") (pin "1") (pintype "passive"))
      (node (ref "TF") (pin "2") (pinfunction "CM/DATA3_2") (pintype "passive"))
      (node (ref "U1") (pin "112") (pinfunction "PC11/UART4_RX/SDIO_D3_112") (pintype "passive"))
    )
    (net (code "71") (name "/SDIO_SCK") (class "Default")
      (node (ref "TF") (pin "5") (pinfunction "CLK_5") (pintype "passive"))
      (node (ref "U1") (pin "113") (pinfunction "PC12/UART5_TX/SDIO_CK_113") (pintype "passive"))
    )
    (net (code "72") (name "/SPI1_CS") (class "Default")
      (node (ref "U1") (pin "40") (pinfunction "PA4/SPI1_NSS/DAC_OUT1/USART2_CK/ADC12_IN4_40") (pintype "passive"))
    )
    (net (code "73") (name "/SPI2_MISO") (class "Default")
      (node (ref "U1") (pin "75") (pinfunction "PB14/SPI2_MISO/USART3_RTS/TIM1_CH2N_75") (pintype "passive"))
      (node (ref "U4") (pin "2") (pinfunction "SO_2") (pintype "passive"))
    )
    (net (code "74") (name "/SPI2_MOSI") (class "Default")
      (node (ref "U1") (pin "76") (pinfunction "PB15/SPI2_MOSI/I2S2_SD/TIM1_CH3N_76") (pintype "passive"))
      (node (ref "U4") (pin "5") (pinfunction "SI_5") (pintype "passive"))
    )
    (net (code "75") (name "/SPI2_SCK") (class "Default")
      (node (ref "U1") (pin "74") (pinfunction "PB13/SPI2_SCK/I2S2_CK/USART3_CTS/TIM1_CH1N_74") (pintype "passive"))
      (node (ref "U4") (pin "6") (pinfunction "CLK_6") (pintype "passive"))
    )
    (net (code "76") (name "/SPK_CTRL") (class "Default")
      (node (ref "R53") (pin "2") (pintype "passive"))
      (node (ref "U17") (pin "1") (pinfunction "CTRL_1") (pintype "passive"))
      (node (ref "U19") (pin "36") (pinfunction "GPIO4/I2S_LROUT_36") (pintype "passive"))
    )
    (net (code "77") (name "/T_CLK") (class "Default")
      (node (ref "2.4'/2.8'LCD1") (pin "34") (pinfunction "CLK_34") (pintype "passive"))
      (node (ref "U1") (pin "29") (pinfunction "PC3/ADC123_IN13_29") (pintype "passive"))
    )
    (net (code "78") (name "/T_CS") (class "Default")
      (node (ref "2.4'/2.8'LCD1") (pin "33") (pinfunction "T_CS_33") (pintype "passive"))
      (node (ref "U1") (pin "44") (pinfunction "PC4/ADC12_IN14_44") (pintype "passive"))
    )
    (net (code "79") (name "/T_MISO") (class "Default")
      (node (ref "2.4'/2.8'LCD1") (pin "29") (pinfunction "MISO_29") (pintype "passive"))
      (node (ref "U1") (pin "26") (pinfunction "PC0/ADC123_IN10_26") (pintype "passive"))
    )
    (net (code "80") (name "/T_MOSI") (class "Default")
      (node (ref "2.4'/2.8'LCD1") (pin "30") (pinfunction "MOSI_30") (pintype "passive"))
      (node (ref "U1") (pin "27") (pinfunction "PC1/ADC123_IN11_27") (pintype "passive"))
    )
    (net (code "81") (name "/T_PEN") (class "Default")
      (node (ref "2.4'/2.8'LCD1") (pin "31") (pinfunction "T_PEN_31") (pintype "passive"))
      (node (ref "U1") (pin "28") (pinfunction "PC2/ADC123_IN12_28") (pintype "passive"))
    )
    (net (code "82") (name "/USART1_RX") (class "Default")
      (node (ref "P4") (pin "1") (pinfunction "1_1") (pintype "passive"))
      (node (ref "U1") (pin "102") (pinfunction "PA10/USART1_RX/TIM1_CH3_102") (pintype "passive"))
    )
    (net (code "83") (name "/USART1_TX") (class "Default")
      (node (ref "P4") (pin "3") (pinfunction "3_3") (pintype "passive"))
      (node (ref "U1") (pin "101") (pinfunction "PA9/USART1_TX/TIM1_CH2_101") (pintype "passive"))
    )
    (net (code "84") (name "/USART2_RX") (class "Default")
      (node (ref "BLE") (pin "4") (pinfunction "TXD_4") (pintype "passive"))
      (node (ref "U1") (pin "37") (pinfunction "PA3/USART2_RX/ADC123_IN3/TIM5_CH4/TIM2_CH4_37") (pintype "passive"))
    )
    (net (code "85") (name "/USART2_TX") (class "Default")
      (node (ref "BLE") (pin "3") (pinfunction "RXD_3") (pintype "passive"))
      (node (ref "U1") (pin "36") (pinfunction "PA2/USART2_TX/ADC123_IN2/TIM5_CH3/TIM2_CH3_36") (pintype "passive"))
    )
    (net (code "86") (name "/USART3_RX") (class "Default")
      (node (ref "BLE") (pin "2") (pinfunction "KEY_2") (pintype "passive"))
      (node (ref "R62") (pin "2") (pintype "passive"))
      (node (ref "U1") (pin "70") (pinfunction "PB11/I2C2_SDA/USART3_RX_70") (pintype "passive"))
    )
    (net (code "87") (name "/USART3_TX") (class "Default")
      (node (ref "BLE") (pin "1") (pinfunction "LED_1") (pintype "passive"))
      (node (ref "R60") (pin "2") (pintype "passive"))
      (node (ref "U1") (pin "69") (pinfunction "PB10/I2C2_SCL/USART3_TX_69") (pintype "passive"))
    )
    (net (code "88") (name "/USB_DM") (class "Default")
      (node (ref "R33") (pin "2") (pintype "passive"))
      (node (ref "U1") (pin "103") (pinfunction "PA11/USART1_CTS/CAN_RX/TIM1_CH4/USBDM_103") (pintype "passive"))
      (node (ref "U5") (pin "4") (pinfunction "R_4") (pintype "output"))
    )
    (net (code "89") (name "/USB_DP") (class "Default")
      (node (ref "R32") (pin "2") (pintype "passive"))
      (node (ref "U1") (pin "104") (pinfunction "PA12/USART1_RTS/CAN_TX/TIM1_ETR/USBDP_104") (pintype "passive"))
      (node (ref "U5") (pin "1") (pinfunction "D_1") (pintype "input"))
    )
    (net (code "90") (name "/VS_DREQ") (class "Default")
      (node (ref "U1") (pin "1") (pinfunction "PE2/TRACECK/FSMC_A23_1") (pintype "passive"))
      (node (ref "U19") (pin "8") (pinfunction "DREQ_8") (pintype "passive"))
    )
    (net (code "91") (name "/VS_MISO") (class "Default")
      (node (ref "U1") (pin "42") (pinfunction "PA6/SPI1_MISO/TIM8_BKIN/ADC12_IN6/TIM3_CH1_42") (pintype "passive"))
      (node (ref "U19") (pin "30") (pinfunction "SO_30") (pintype "passive"))
    )
    (net (code "92") (name "/VS_MOSI") (class "Default")
      (node (ref "U1") (pin "43") (pinfunction "PA7/SPI1_MOSI/TIM8_CH1N/ADC12_IN7/TIM3_CH2_43") (pintype "passive"))
      (node (ref "U19") (pin "29") (pinfunction "S1_29") (pintype "passive"))
    )
    (net (code "93") (name "/VS_RST") (class "Default")
      (node (ref "U1") (pin "2") (pinfunction "PE3/TRACED0/FSMC_A19_2") (pintype "passive"))
      (node (ref "U19") (pin "3") (pinfunction "XREST_3") (pintype "passive"))
    )
    (net (code "94") (name "/VS_SCK") (class "Default")
      (node (ref "U1") (pin "41") (pinfunction "PA5/SPI1_SCK/DAC_OUT2/ADC12_IN5_41") (pintype "passive"))
      (node (ref "U19") (pin "28") (pinfunction "SCLK_28") (pintype "passive"))
    )
    (net (code "95") (name "/VS_XCS") (class "Default")
      (node (ref "U1") (pin "3") (pinfunction "PE4/TRACED1/FSMC_A20_3") (pintype "passive"))
      (node (ref "U19") (pin "23") (pinfunction "XCS_23") (pintype "passive"))
    )
    (net (code "96") (name "/VS_XDCS") (class "Default")
      (node (ref "U1") (pin "4") (pinfunction "PE5/TRACED2/FSMC_A21_4") (pintype "passive"))
      (node (ref "U19") (pin "13") (pinfunction "XDCS/BSYNC_13") (pintype "passive"))
    )
    (net (code "97") (name "GND") (class "Default")
      (node (ref "2.4'/2.8'LCD1") (pin "22") (pinfunction "GND_22") (pintype "passive"))
      (node (ref "2.4'/2.8'LCD1") (pin "26") (pinfunction "GND_26") (pintype "passive"))
      (node (ref "2.4'/2.8'LCD1") (pin "27") (pinfunction "GND_27") (pintype "passive"))
      (node (ref "BAT") (pin "2") (pinfunction "GND_2") (pintype "passive"))
      (node (ref "BAT2") (pin "2") (pinfunction "GND_2") (pintype "passive"))
      (node (ref "BLE") (pin "5") (pinfunction "GND_5") (pintype "passive"))
      (node (ref "C1") (pin "1") (pintype "passive"))
      (node (ref "C10") (pin "1") (pintype "passive"))
      (node (ref "C103") (pin "1") (pintype "passive"))
      (node (ref "C104") (pin "1") (pintype "passive"))
      (node (ref "C11") (pin "1") (pintype "passive"))
      (node (ref "C12") (pin "1") (pintype "passive"))
      (node (ref "C13") (pin "1") (pintype "passive"))
      (node (ref "C14") (pin "1") (pintype "passive"))
      (node (ref "C15") (pin "1") (pintype "passive"))
      (node (ref "C16") (pin "1") (pintype "passive"))
      (node (ref "C17") (pin "1") (pintype "passive"))
      (node (ref "C18") (pin "1") (pintype "passive"))
      (node (ref "C19") (pin "1") (pintype "passive"))
      (node (ref "C2") (pin "1") (pintype "passive"))
      (node (ref "C20") (pin "1") (pintype "passive"))
      (node (ref "C21") (pin "1") (pintype "passive"))
      (node (ref "C29") (pin "2") (pintype "passive"))
      (node (ref "C3") (pin "1") (pintype "passive"))
      (node (ref "C30") (pin "2") (pintype "passive"))
      (node (ref "C31") (pin "2") (pintype "passive"))
      (node (ref "C32") (pin "1") (pintype "passive"))
      (node (ref "C33") (pin "2") (pintype "passive"))
      (node (ref "C34") (pin "2") (pintype "passive"))
      (node (ref "C35") (pin "1") (pintype "passive"))
      (node (ref "C36") (pin "1") (pintype "passive"))
      (node (ref "C4") (pin "2") (pintype "passive"))
      (node (ref "C42") (pin "1") (pintype "passive"))
      (node (ref "C43") (pin "1") (pintype "passive"))
      (node (ref "C44") (pin "2") (pinfunction "GND_2") (pintype "passive"))
      (node (ref "C45") (pin "1") (pintype "passive"))
      (node (ref "C48") (pin "1") (pintype "passive"))
      (node (ref "C5") (pin "1") (pintype "passive"))
      (node (ref "C50") (pin "2") (pintype "passive"))
      (node (ref "C51") (pin "2") (pintype "passive"))
      (node (ref "C54") (pin "2") (pintype "passive"))
      (node (ref "C55") (pin "1") (pintype "passive"))
      (node (ref "C56") (pin "1") (pintype "passive"))
      (node (ref "C57") (pin "2") (pintype "passive"))
      (node (ref "C6") (pin "1") (pintype "passive"))
      (node (ref "C60") (pin "1") (pintype "passive"))
      (node (ref "C61") (pin "1") (pintype "passive"))
      (node (ref "C62") (pin "1") (pintype "passive"))
      (node (ref "C65") (pin "1") (pintype "passive"))
      (node (ref "C66") (pin "1") (pintype "passive"))
      (node (ref "C67") (pin "1") (pintype "passive"))
      (node (ref "C7") (pin "1") (pintype "passive"))
      (node (ref "C72") (pin "1") (pintype "passive"))
      (node (ref "C74") (pin "1") (pintype "passive"))
      (node (ref "C75") (pin "1") (pintype "passive"))
      (node (ref "C76") (pin "1") (pintype "passive"))
      (node (ref "C77") (pin "2") (pintype "passive"))
      (node (ref "C78") (pin "2") (pintype "passive"))
      (node (ref "C79") (pin "2") (pintype "passive"))
      (node (ref "C8") (pin "1") (pintype "passive"))
      (node (ref "C80") (pin "1") (pintype "passive"))
      (node (ref "C87") (pin "1") (pintype "passive"))
      (node (ref "C88") (pin "1") (pintype "passive"))
      (node (ref "C89") (pin "1") (pintype "passive"))
      (node (ref "C9") (pin "1") (pintype "passive"))
      (node (ref "C91") (pin "1") (pintype "passive"))
      (node (ref "C92") (pin "1") (pintype "passive"))
      (node (ref "C93") (pin "1") (pintype "passive"))
      (node (ref "C94") (pin "2") (pintype "passive"))
      (node (ref "IPX1") (pin "1") (pinfunction "GND_1") (pintype "passive"))
      (node (ref "IPX1") (pin "3") (pinfunction "GND_3") (pintype "passive"))
      (node (ref "KEY0") (pin "2") (pinfunction "2_2") (pintype "passive"))
      (node (ref "KEY1") (pin "2") (pinfunction "2_2") (pintype "passive"))
      (node (ref "KEY2") (pin "2") (pinfunction "2_2") (pintype "passive"))
      (node (ref "P10") (pin "1") (pinfunction "1_1") (pintype "passive"))
      (node (ref "R11") (pin "2") (pintype "passive"))
      (node (ref "R12") (pin "2") (pintype "passive"))
      (node (ref "R13") (pin "2") (pintype "passive"))
      (node (ref "R53") (pin "1") (pintype "passive"))
      (node (ref "R70") (pin "1") (pintype "passive"))
      (node (ref "R76") (pin "2") (pintype "passive"))
      (node (ref "RESET") (pin "2") (pinfunction "2_2") (pintype "passive"))
      (node (ref "TF") (pin "10") (pinfunction "10_10") (pintype "passive"))
      (node (ref "TF") (pin "11") (pinfunction "11_11") (pintype "passive"))
      (node (ref "TF") (pin "12") (pinfunction "12_12") (pintype "passive"))
      (node (ref "TF") (pin "13") (pinfunction "13_13") (pintype "passive"))
      (node (ref "TF") (pin "6") (pinfunction "VSS_6") (pintype "passive"))
      (node (ref "U1") (pin "107") (pinfunction "VSS_107") (pintype "passive"))
      (node (ref "U1") (pin "120") (pinfunction "VSS_120") (pintype "passive"))
      (node (ref "U1") (pin "130") (pinfunction "VSS_130") (pintype "passive"))
      (node (ref "U1") (pin "143") (pinfunction "VSS_143") (pintype "passive"))
      (node (ref "U1") (pin "16") (pinfunction "VSS_16") (pintype "passive"))
      (node (ref "U1") (pin "30") (pinfunction "VSSA_30") (pintype "passive"))
      (node (ref "U1") (pin "31") (pinfunction "Vref-_31") (pintype "passive"))
      (node (ref "U1") (pin "38") (pinfunction "VSS_38") (pintype "passive"))
      (node (ref "U1") (pin "51") (pinfunction "VSS_51") (pintype "passive"))
      (node (ref "U1") (pin "61") (pinfunction "VSS_61") (pintype "passive"))
      (node (ref "U1") (pin "71") (pinfunction "VSS_71") (pintype "passive"))
      (node (ref "U1") (pin "83") (pinfunction "VSS_83") (pintype "passive"))
      (node (ref "U1") (pin "94") (pinfunction "VSS_94") (pintype "passive"))
      (node (ref "U12") (pin "1") (pinfunction "GND_1") (pintype "passive"))
      (node (ref "U14") (pin "1") (pinfunction "GND_1") (pintype "passive"))
      (node (ref "U15") (pin "1") (pinfunction "GND_1") (pintype "passive"))
      (node (ref "U17") (pin "7") (pinfunction "GND_7") (pintype "passive"))
      (node (ref "U19") (pin "16") (pinfunction "DGND_16") (pintype "passive"))
      (node (ref "U19") (pin "20") (pinfunction "DGND_20") (pintype "passive"))
      (node (ref "U19") (pin "21") (pinfunction "DGND_21") (pintype "passive"))
      (node (ref "U19") (pin "22") (pinfunction "DGND_22") (pintype "passive"))
      (node (ref "U19") (pin "35") (pinfunction "DGND_35") (pintype "passive"))
      (node (ref "U19") (pin "37") (pinfunction "AGND_37") (pintype "passive"))
      (node (ref "U19") (pin "4") (pinfunction "DGND_4") (pintype "passive"))
      (node (ref "U19") (pin "40") (pinfunction "AGND_40") (pintype "passive"))
      (node (ref "U19") (pin "41") (pinfunction "AGND_41") (pintype "passive"))
      (node (ref "U19") (pin "47") (pinfunction "AGND_47") (pintype "passive"))
      (node (ref "U2") (pin "12") (pinfunction "GND_12") (pintype "passive"))
      (node (ref "U2") (pin "34") (pinfunction "GND_34") (pintype "passive"))
      (node (ref "U3") (pin "1") (pinfunction "A0_1") (pintype "passive"))
      (node (ref "U3") (pin "2") (pinfunction "A1_2") (pintype "passive"))
      (node (ref "U3") (pin "3") (pinfunction "A2_3") (pintype "passive"))
      (node (ref "U3") (pin "4") (pinfunction "GND_4") (pintype "passive"))
      (node (ref "U3") (pin "7") (pinfunction "WP_7") (pintype "passive"))
      (node (ref "U4") (pin "4") (pinfunction "GND_4") (pintype "passive"))
      (node (ref "U5") (pin "3") (pinfunction "VCC_3") (pintype "power_in"))
      (node (ref "U5") (pin "8") (pinfunction "RS_8") (pintype "input"))
      (node (ref "U6") (pin "3") (pinfunction "NC_3") (pintype "passive"))
      (node (ref "U6") (pin "4") (pinfunction "GND_4") (pintype "passive"))
      (node (ref "U7") (pin "10") (pinfunction "GND_10") (pintype "passive"))
      (node (ref "U7") (pin "12") (pinfunction "GND_12") (pintype "passive"))
      (node (ref "U7") (pin "13") (pinfunction "GND_13") (pintype "passive"))
      (node (ref "U7") (pin "24") (pinfunction "GND_24") (pintype "passive"))
      (node (ref "U8") (pin "2") (pinfunction "GND_2") (pintype "passive"))
      (node (ref "USB_232") (pin "5") (pinfunction "GND_5") (pintype "passive"))
      (node (ref "USB_SLAVE") (pin "5") (pinfunction "GND_5") (pintype "passive"))
    )
    (net (code "98") (name "Net-(BAT-VCC)") (class "Default")
      (node (ref "BAT") (pin "1") (pinfunction "VCC_1") (pintype "passive"))
      (node (ref "D2") (pin "1") (pintype "passive"))
    )
    (net (code "99") (name "Net-(BAT2-VCC)") (class "Default")
      (node (ref "BAT2") (pin "1") (pinfunction "VCC_1") (pintype "passive"))
      (node (ref "R63") (pin "1") (pintype "passive"))
      (node (ref "U7") (pin "22") (pinfunction "V_BCKP_22") (pintype "passive"))
    )
    (net (code "100") (name "Net-(C60-Pad2)") (class "Default")
      (node (ref "C60") (pin "2") (pintype "passive"))
      (node (ref "R50") (pin "1") (pintype "passive"))
    )
    (net (code "101") (name "Net-(C61-Pad2)") (class "Default")
      (node (ref "C61") (pin "2") (pintype "passive"))
      (node (ref "R51") (pin "1") (pintype "passive"))
    )
    (net (code "102") (name "Net-(C62-Pad2)") (class "Default")
      (node (ref "C62") (pin "2") (pintype "passive"))
      (node (ref "R52") (pin "1") (pintype "passive"))
    )
    (net (code "103") (name "Net-(C72-Pad2)") (class "Default")
      (node (ref "C72") (pin "2") (pintype "passive"))
      (node (ref "R58") (pin "1") (pintype "passive"))
    )
    (net (code "104") (name "Net-(C73-Pad2)") (class "Default")
      (node (ref "C73") (pin "2") (pintype "passive"))
      (node (ref "R61") (pin "1") (pintype "passive"))
    )
    (net (code "105") (name "Net-(C77-Pad1)") (class "Default")
      (node (ref "C77") (pin "1") (pintype "passive"))
      (node (ref "C78") (pin "1") (pintype "passive"))
      (node (ref "C79") (pin "1") (pintype "passive"))
      (node (ref "C80") (pin "2") (pintype "passive"))
      (node (ref "U15") (pin "2") (pinfunction "OUT_2") (pintype "passive"))
      (node (ref "U15") (pin "4") (pinfunction "OUT_4") (pintype "passive"))
      (node (ref "U19") (pin "24") (pinfunction "CVDD_24") (pintype "passive"))
      (node (ref "U19") (pin "31") (pinfunction "CVDD_31") (pintype "passive"))
      (node (ref "U19") (pin "5") (pinfunction "CVDD_5") (pintype "passive"))
      (node (ref "U19") (pin "7") (pinfunction "CVDD_7") (pintype "passive"))
    )
    (net (code "106") (name "Net-(C89-Pad2)") (class "Default")
      (node (ref "C89") (pin "2") (pintype "passive"))
      (node (ref "C90") (pin "2") (pintype "passive"))
      (node (ref "R71") (pin "1") (pintype "passive"))
      (node (ref "R73") (pin "2") (pintype "passive"))
    )
    (net (code "107") (name "Net-(C90-Pad1)") (class "Default")
      (node (ref "C90") (pin "1") (pintype "passive"))
      (node (ref "R75") (pin "1") (pintype "passive"))
      (node (ref "R76") (pin "1") (pintype "passive"))
    )
    (net (code "108") (name "Net-(D3-Pad2)") (class "Default")
      (node (ref "D3") (pin "2") (pintype "passive"))
      (node (ref "R63") (pin "2") (pintype "passive"))
    )
    (net (code "109") (name "Net-(DS1-A)") (class "Default")
      (node (ref "DS1") (pin "1") (pinfunction "A_1") (pintype "passive"))
      (node (ref "R20") (pin "2") (pintype "passive"))
    )
    (net (code "110") (name "Net-(DS2-A)") (class "Default")
      (node (ref "DS2") (pin "1") (pinfunction "A_1") (pintype "passive"))
      (node (ref "R22") (pin "2") (pintype "passive"))
    )
    (net (code "111") (name "Net-(DS3-A)") (class "Default")
      (node (ref "DS3") (pin "1") (pinfunction "A_1") (pintype "passive"))
      (node (ref "R24") (pin "2") (pintype "passive"))
    )
    (net (code "112") (name "Net-(IPX1-DATA)") (class "Default")
      (node (ref "IPX1") (pin "2") (pinfunction "DATA_2") (pintype "passive"))
      (node (ref "U7") (pin "11") (pinfunction "RF_IN_11") (pintype "passive"))
    )
    (net (code "113") (name "Net-(MIC-GND)") (class "Default")
      (node (ref "C96") (pin "1") (pintype "passive"))
      (node (ref "C99") (pin "2") (pintype "passive"))
      (node (ref "MIC") (pin "2") (pinfunction "GND_2") (pintype "passive"))
      (node (ref "R75") (pin "2") (pintype "passive"))
    )
    (net (code "114") (name "Net-(MIC-VCC)") (class "Default")
      (node (ref "C95") (pin "1") (pintype "passive"))
      (node (ref "C96") (pin "2") (pintype "passive"))
      (node (ref "MIC") (pin "1") (pinfunction "VCC_1") (pintype "passive"))
      (node (ref "R73") (pin "1") (pintype "passive"))
    )
    (net (code "115") (name "Net-(P10-Pad3)") (class "Default")
      (node (ref "P10") (pin "3") (pinfunction "3_3") (pintype "passive"))
      (node (ref "R5") (pin "1") (pintype "passive"))
    )
    (net (code "116") (name "Net-(PHONE-CHL)") (class "Default")
      (node (ref "PHONE") (pin "1") (pinfunction "CHL_1") (pintype "passive"))
      (node (ref "R51") (pin "2") (pintype "passive"))
      (node (ref "U19") (pin "39") (pinfunction "RIGHT_39") (pintype "passive"))
    )
    (net (code "117") (name "Net-(PHONE-CHR)") (class "Default")
      (node (ref "C73") (pin "1") (pintype "passive"))
      (node (ref "PHONE") (pin "2") (pinfunction "CHR_2") (pintype "passive"))
      (node (ref "R50") (pin "2") (pintype "passive"))
      (node (ref "U19") (pin "46") (pinfunction "LEFT_46") (pintype "passive"))
    )
    (net (code "118") (name "Net-(PHONE-COM)") (class "Default")
      (node (ref "PHONE") (pin "3") (pinfunction "COM_3") (pintype "passive"))
      (node (ref "R52") (pin "2") (pintype "passive"))
      (node (ref "U19") (pin "42") (pinfunction "GBUF_42") (pintype "passive"))
    )
    (net (code "119") (name "Net-(PPS1-Pad1)") (class "Default")
      (node (ref "PPS1") (pin "1") (pinfunction "1_1") (pintype "passive"))
      (node (ref "R64") (pin "2") (pintype "passive"))
    )
    (net (code "120") (name "Net-(U1-OSC_IN)") (class "Default")
      (node (ref "C7") (pin "2") (pintype "passive"))
      (node (ref "R2") (pin "2") (pintype "passive"))
      (node (ref "U1") (pin "23") (pinfunction "OSC_IN_23") (pintype "passive"))
      (node (ref "Y1") (pin "2") (pinfunction "OSC2_2") (pintype "passive"))
    )
    (net (code "121") (name "Net-(U1-OSC_OUT)") (class "Default")
      (node (ref "C6") (pin "2") (pintype "passive"))
      (node (ref "R2") (pin "1") (pintype "passive"))
      (node (ref "U1") (pin "24") (pinfunction "OSC_OUT_24") (pintype "passive"))
      (node (ref "Y1") (pin "1") (pinfunction "OSC1_1") (pintype "passive"))
    )
    (net (code "122") (name "Net-(U1-PC14-OSC32_IN)") (class "Default")
      (node (ref "C3") (pin "2") (pintype "passive"))
      (node (ref "U1") (pin "8") (pinfunction "PC14-OSC32_IN_8") (pintype "passive"))
      (node (ref "Y2") (pin "1") (pinfunction "OSC1_1") (pintype "passive"))
    )
    (net (code "123") (name "Net-(U1-PC15-OSC32_OUT)") (class "Default")
      (node (ref "C4") (pin "1") (pintype "passive"))
      (node (ref "U1") (pin "9") (pinfunction "PC15-OSC32_OUT_9") (pintype "passive"))
      (node (ref "Y2") (pin "2") (pinfunction "OSC2_2") (pintype "passive"))
    )
    (net (code "124") (name "Net-(U1-VBAT)") (class "Default")
      (node (ref "C5") (pin "2") (pintype "passive"))
      (node (ref "D1") (pin "2") (pintype "passive"))
      (node (ref "D2") (pin "2") (pintype "passive"))
      (node (ref "U1") (pin "6") (pinfunction "VBAT_6") (pintype "passive"))
    )
    (net (code "125") (name "Net-(U1-VDDA)") (class "Default")
      (node (ref "C8") (pin "2") (pintype "passive"))
      (node (ref "C9") (pin "2") (pintype "passive"))
      (node (ref "R4") (pin "1") (pintype "passive"))
      (node (ref "U1") (pin "32") (pinfunction "Vref+_32") (pintype "passive"))
      (node (ref "U1") (pin "33") (pinfunction "VDDA_33") (pintype "passive"))
    )
    (net (code "126") (name "Net-(U5-CANH)") (class "Default")
      (node (ref "P6") (pin "1") (pinfunction "1_1") (pintype "passive"))
      (node (ref "R80") (pin "2") (pintype "passive"))
      (node (ref "U5") (pin "7") (pinfunction "CANH_7") (pintype "bidirectional"))
    )
    (net (code "127") (name "Net-(U5-CANL)") (class "Default")
      (node (ref "P6") (pin "2") (pinfunction "2_2") (pintype "passive"))
      (node (ref "R80") (pin "1") (pintype "passive"))
      (node (ref "U5") (pin "6") (pinfunction "CANL_6") (pintype "bidirectional"))
    )
    (net (code "128") (name "Net-(U7-1PPS)") (class "Default")
      (node (ref "PPS1") (pin "2") (pinfunction "2_2") (pintype "passive"))
      (node (ref "U7") (pin "3") (pinfunction "1PPS_3") (pintype "passive"))
    )
    (net (code "129") (name "Net-(U7-RXD)") (class "Default")
      (node (ref "R60") (pin "1") (pintype "passive"))
      (node (ref "U7") (pin "21") (pinfunction "RXD_21") (pintype "passive"))
    )
    (net (code "130") (name "Net-(U7-TXD)") (class "Default")
      (node (ref "R62") (pin "1") (pintype "passive"))
      (node (ref "U7") (pin "20") (pinfunction "TXD_20") (pintype "passive"))
    )
    (net (code "131") (name "Net-(U7-VCC)") (class "Default")
      (node (ref "C32") (pin "2") (pintype "passive"))
      (node (ref "C33") (pin "1") (pintype "passive"))
      (node (ref "D3") (pin "1") (pintype "passive"))
      (node (ref "U7") (pin "23") (pinfunction "VCC_23") (pintype "passive"))
      (node (ref "U8") (pin "5") (pinfunction "VOUT_5") (pintype "passive"))
    )
    (net (code "132") (name "Net-(U8-BP)") (class "Default")
      (node (ref "C30") (pin "1") (pintype "passive"))
      (node (ref "U8") (pin "4") (pinfunction "BP_4") (pintype "passive"))
    )
    (net (code "133") (name "Net-(U12-IN)") (class "Default")
      (node (ref "C45") (pin "2") (pintype "passive"))
      (node (ref "P1") (pin "1") (pinfunction "1_1") (pintype "passive"))
      (node (ref "U12") (pin "3") (pinfunction "IN_3") (pintype "passive"))
    )
    (net (code "134") (name "Net-(U14-D+)") (class "Default")
      (node (ref "U14") (pin "5") (pinfunction "D+_5") (pintype "passive"))
      (node (ref "USB_232") (pin "3") (pinfunction "D+_3") (pintype "passive"))
    )
    (net (code "135") (name "Net-(U14-D-)") (class "Default")
      (node (ref "U14") (pin "6") (pinfunction "D-_6") (pintype "passive"))
      (node (ref "USB_232") (pin "2") (pinfunction "D-_2") (pintype "passive"))
    )
    (net (code "136") (name "Net-(U14-V3)") (class "Default")
      (node (ref "C55") (pin "2") (pintype "passive"))
      (node (ref "U14") (pin "4") (pinfunction "V3_4") (pintype "passive"))
    )
    (net (code "137") (name "Net-(U14-XI)") (class "Default")
      (node (ref "C56") (pin "2") (pintype "passive"))
      (node (ref "U14") (pin "7") (pinfunction "XI_7") (pintype "passive"))
      (node (ref "Y3") (pin "1") (pinfunction "OSC1_1") (pintype "passive"))
    )
    (net (code "138") (name "Net-(U14-XO)") (class "Default")
      (node (ref "C57") (pin "1") (pintype "passive"))
      (node (ref "U14") (pin "8") (pinfunction "XO_8") (pintype "passive"))
      (node (ref "Y3") (pin "2") (pinfunction "OSC2_2") (pintype "passive"))
    )
    (net (code "139") (name "Net-(U17-BYPASS)") (class "Default")
      (node (ref "C67") (pin "2") (pintype "passive"))
      (node (ref "U17") (pin "2") (pinfunction "BYPASS_2") (pintype "passive"))
    )
    (net (code "140") (name "Net-(U17-IN+)") (class "Default")
      (node (ref "R61") (pin "2") (pintype "passive"))
      (node (ref "U17") (pin "4") (pinfunction "IN+_4") (pintype "passive"))
    )
    (net (code "141") (name "Net-(U17-IN-)") (class "Default")
      (node (ref "R58") (pin "2") (pintype "passive"))
      (node (ref "U17") (pin "3") (pinfunction "IN-_3") (pintype "passive"))
    )
    (net (code "142") (name "Net-(U17-OUT+)") (class "Default")
      (node (ref "SP+") (pin "1") (pinfunction "1_1") (pintype "passive"))
      (node (ref "U17") (pin "5") (pinfunction "OUT+_5") (pintype "passive"))
    )
    (net (code "143") (name "Net-(U17-OUT-)") (class "Default")
      (node (ref "SP-") (pin "1") (pinfunction "1_1") (pintype "passive"))
      (node (ref "U17") (pin "8") (pinfunction "OUT-_8") (pintype "passive"))
    )
    (net (code "144") (name "Net-(U19-GPIO0)") (class "Default")
      (node (ref "R70") (pin "2") (pintype "passive"))
      (node (ref "U19") (pin "33") (pinfunction "GPIO0_33") (pintype "passive"))
      (node (ref "U19") (pin "34") (pinfunction "GPIO1_34") (pintype "passive"))
    )
    (net (code "145") (name "Net-(U19-LINE2)") (class "Default")
      (node (ref "C103") (pin "2") (pintype "passive"))
      (node (ref "U19") (pin "48") (pinfunction "LINE2_48") (pintype "passive"))
    )
    (net (code "146") (name "Net-(U19-MICN)") (class "Default")
      (node (ref "C99") (pin "1") (pintype "passive"))
      (node (ref "U19") (pin "2") (pinfunction "MICN_2") (pintype "passive"))
    )
    (net (code "147") (name "Net-(U19-MICP{slash}LINE1)") (class "Default")
      (node (ref "C104") (pin "2") (pintype "passive"))
      (node (ref "C95") (pin "2") (pintype "passive"))
      (node (ref "U19") (pin "1") (pinfunction "MICP/LINE1_1") (pintype "passive"))
    )
    (net (code "148") (name "Net-(U19-RCAP)") (class "Default")
      (node (ref "C94") (pin "1") (pintype "passive"))
      (node (ref "U19") (pin "44") (pinfunction "RCAP_44") (pintype "passive"))
    )
    (net (code "149") (name "Net-(U19-RX)") (class "Default")
      (node (ref "R68") (pin "1") (pintype "passive"))
      (node (ref "U19") (pin "26") (pinfunction "RX_26") (pintype "passive"))
    )
    (net (code "150") (name "Net-(U19-XIALO)") (class "Default")
      (node (ref "C88") (pin "2") (pintype "passive"))
      (node (ref "R69") (pin "2") (pintype "passive"))
      (node (ref "U19") (pin "17") (pinfunction "XIALO_17") (pintype "passive"))
      (node (ref "Y4") (pin "2") (pinfunction "OSC2_2") (pintype "passive"))
    )
    (net (code "151") (name "Net-(U19-XTALI)") (class "Default")
      (node (ref "C87") (pin "2") (pintype "passive"))
      (node (ref "R69") (pin "1") (pintype "passive"))
      (node (ref "U19") (pin "18") (pinfunction "XTALI_18") (pintype "passive"))
      (node (ref "Y4") (pin "1") (pinfunction "OSC1_1") (pintype "passive"))
    )
    (net (code "152") (name "Net-(USB_SLAVE-D+)") (class "Default")
      (node (ref "R32") (pin "1") (pintype "passive"))
      (node (ref "R35") (pin "1") (pintype "passive"))
      (node (ref "USB_SLAVE") (pin "3") (pinfunction "D+_3") (pintype "passive"))
    )
    (net (code "153") (name "Net-(USB_SLAVE-D-)") (class "Default")
      (node (ref "R33") (pin "1") (pintype "passive"))
      (node (ref "USB_SLAVE") (pin "2") (pinfunction "D-_2") (pintype "passive"))
    )
    (net (code "154") (name "VCC") (class "Default")
      (node (ref "C48") (pin "2") (pintype "passive"))
      (node (ref "U5") (pin "2") (pinfunction "GND_2") (pintype "power_in"))
    )
    (net (code "155") (name "VCC3.3") (class "Default")
      (node (ref "2.4'/2.8'LCD1") (pin "24") (pinfunction "VDD3.3_24") (pintype "passive"))
      (node (ref "2.4'/2.8'LCD1") (pin "25") (pinfunction "VDD3.3_25") (pintype "passive"))
      (node (ref "C1") (pin "2") (pintype "passive"))
      (node (ref "C11") (pin "2") (pintype "passive"))
      (node (ref "C12") (pin "2") (pintype "passive"))
      (node (ref "C13") (pin "2") (pintype "passive"))
      (node (ref "C14") (pin "2") (pintype "passive"))
      (node (ref "C15") (pin "2") (pintype "passive"))
      (node (ref "C16") (pin "2") (pintype "passive"))
      (node (ref "C17") (pin "2") (pintype "passive"))
      (node (ref "C18") (pin "2") (pintype "passive"))
      (node (ref "C19") (pin "2") (pintype "passive"))
      (node (ref "C2") (pin "2") (pintype "passive"))
      (node (ref "C20") (pin "2") (pintype "passive"))
      (node (ref "C21") (pin "2") (pintype "passive"))
      (node (ref "C29") (pin "1") (pintype "passive"))
      (node (ref "C31") (pin "1") (pintype "passive"))
      (node (ref "C35") (pin "2") (pintype "passive"))
      (node (ref "C36") (pin "2") (pintype "passive"))
      (node (ref "C43") (pin "2") (pintype "passive"))
      (node (ref "C44") (pin "1") (pinfunction "VCC_1") (pintype "passive"))
      (node (ref "D1") (pin "1") (pintype "passive"))
      (node (ref "R1") (pin "2") (pintype "passive"))
      (node (ref "R18") (pin "2") (pintype "passive"))
      (node (ref "R20") (pin "1") (pintype "passive"))
      (node (ref "R21") (pin "2") (pintype "passive"))
      (node (ref "R22") (pin "1") (pintype "passive"))
      (node (ref "R23") (pin "2") (pintype "passive"))
      (node (ref "R24") (pin "1") (pintype "passive"))
      (node (ref "R27") (pin "1") (pintype "passive"))
      (node (ref "R28") (pin "2") (pintype "passive"))
      (node (ref "R29") (pin "2") (pintype "passive"))
      (node (ref "R3") (pin "2") (pintype "passive"))
      (node (ref "R35") (pin "2") (pintype "passive"))
      (node (ref "R4") (pin "2") (pintype "passive"))
      (node (ref "R42") (pin "2") (pintype "passive"))
      (node (ref "R5") (pin "2") (pintype "passive"))
      (node (ref "R6") (pin "2") (pintype "passive"))
      (node (ref "R64") (pin "1") (pintype "passive"))
      (node (ref "R67") (pin "2") (pintype "passive"))
      (node (ref "TF") (pin "4") (pinfunction "VDD_4") (pintype "passive"))
      (node (ref "U1") (pin "108") (pinfunction "VDD_108") (pintype "passive"))
      (node (ref "U1") (pin "121") (pinfunction "VDD_121") (pintype "passive"))
      (node (ref "U1") (pin "131") (pinfunction "VDD_131") (pintype "passive"))
      (node (ref "U1") (pin "144") (pinfunction "VDD_144") (pintype "passive"))
      (node (ref "U1") (pin "17") (pinfunction "VDD_17") (pintype "passive"))
      (node (ref "U1") (pin "39") (pinfunction "VDD_39") (pintype "passive"))
      (node (ref "U1") (pin "52") (pinfunction "VDD_52") (pintype "passive"))
      (node (ref "U1") (pin "62") (pinfunction "VDD_62") (pintype "passive"))
      (node (ref "U1") (pin "72") (pinfunction "VDD_72") (pintype "passive"))
      (node (ref "U1") (pin "84") (pinfunction "VDD_84") (pintype "passive"))
      (node (ref "U1") (pin "95") (pinfunction "VDD_95") (pintype "passive"))
      (node (ref "U12") (pin "2") (pinfunction "OUT_2") (pintype "passive"))
      (node (ref "U12") (pin "4") (pinfunction "OUT_4") (pintype "passive"))
      (node (ref "U2") (pin "11") (pinfunction "VDD_11") (pintype "passive"))
      (node (ref "U2") (pin "33") (pinfunction "VDD_33") (pintype "passive"))
      (node (ref "U3") (pin "8") (pinfunction "VCC1_8") (pintype "passive"))
      (node (ref "U4") (pin "3") (pinfunction "WP#_3") (pintype "passive"))
      (node (ref "U4") (pin "7") (pinfunction "HOLD_7") (pintype "passive"))
      (node (ref "U4") (pin "8") (pinfunction "VCC_8") (pintype "passive"))
      (node (ref "U6") (pin "1") (pinfunction "VCC_1") (pintype "passive"))
    )
    (net (code "156") (name "VCC5") (class "Default")
      (node (ref "2.4'/2.8'LCD1") (pin "28") (pinfunction "BL_VDD_28") (pintype "passive"))
      (node (ref "BLE") (pin "6") (pinfunction "VCC_6") (pintype "passive"))
      (node (ref "C34") (pin "1") (pintype "passive"))
      (node (ref "C50") (pin "1") (pintype "passive"))
      (node (ref "C51") (pin "1") (pintype "passive"))
      (node (ref "C54") (pin "1") (pintype "passive"))
      (node (ref "C65") (pin "2") (pintype "passive"))
      (node (ref "C66") (pin "2") (pintype "passive"))
      (node (ref "P1") (pin "2") (pinfunction "2_2") (pintype "passive"))
      (node (ref "U14") (pin "16") (pinfunction "VCC_16") (pintype "passive"))
      (node (ref "U15") (pin "3") (pinfunction "IN_3") (pintype "passive"))
      (node (ref "U17") (pin "6") (pinfunction "VDD_6") (pintype "passive"))
      (node (ref "U8") (pin "1") (pinfunction "VIN_1") (pintype "passive"))
      (node (ref "U8") (pin "3") (pinfunction "EN_3") (pintype "passive"))
      (node (ref "USB_232") (pin "1") (pinfunction "VCC_1") (pintype "passive"))
      (node (ref "USB_SLAVE") (pin "1") (pinfunction "VCC_1") (pintype "passive"))
    )
    (net (code "157") (name "unconnected-(2.4'/2.8'LCD1-MO-Pad32)") (class "Default")
      (node (ref "2.4'/2.8'LCD1") (pin "32") (pinfunction "MO_32") (pintype "passive+no_connect"))
    )
    (net (code "158") (name "unconnected-(TF-Pad9)") (class "Default")
      (node (ref "TF") (pin "9") (pinfunction "9_9") (pintype "passive"))
    )
    (net (code "159") (name "unconnected-(TF-Pad14)") (class "Default")
      (node (ref "TF") (pin "14") (pinfunction "14_14") (pintype "passive"))
    )
    (net (code "160") (name "unconnected-(TF-Pad15)") (class "Default")
      (node (ref "TF") (pin "15") (pinfunction "15_15") (pintype "passive"))
    )
    (net (code "161") (name "unconnected-(U1-NC-Pad106)") (class "Default")
      (node (ref "U1") (pin "106") (pinfunction "NC_106") (pintype "passive+no_connect"))
    )
    (net (code "162") (name "unconnected-(U1-PA8{slash}USART1_CK{slash}TIM1_CH1{slash}MCO-Pad100)") (class "Default")
      (node (ref "U1") (pin "100") (pinfunction "PA8/USART1_CK/TIM1_CH1/MCO_100") (pintype "passive"))
    )
    (net (code "163") (name "unconnected-(U1-PA15{slash}JTDI{slash}SPI3_NSS{slash}I2S3_WS-Pad110)") (class "Default")
      (node (ref "U1") (pin "110") (pinfunction "PA15/JTDI/SPI3_NSS/I2S3_WS_110") (pintype "passive"))
    )
    (net (code "164") (name "unconnected-(U1-PB0{slash}ADC12_IN8{slash}TIM3_CH3{slash}TIM8_CH2N-Pad46)") (class "Default")
      (node (ref "U1") (pin "46") (pinfunction "PB0/ADC12_IN8/TIM3_CH3/TIM8_CH2N_46") (pintype "passive"))
    )
    (net (code "165") (name "unconnected-(U1-PB1{slash}ADC12_IN9{slash}TIM3_CH4{slash}TIM8_CH3N-Pad47)") (class "Default")
      (node (ref "U1") (pin "47") (pinfunction "PB1/ADC12_IN9/TIM3_CH4/TIM8_CH3N_47") (pintype "passive"))
    )
    (net (code "166") (name "unconnected-(U1-PB5{slash}I2C1_SMBAI{slash}SPI3_MOSI{slash}I2S3_SD-Pad135)") (class "Default")
      (node (ref "U1") (pin "135") (pinfunction "PB5/I2C1_SMBAI/SPI3_MOSI/I2S3_SD_135") (pintype "passive"))
    )
    (net (code "167") (name "unconnected-(U1-PB8{slash}TIM4_CH3{slash}SDIO_D4-Pad139)") (class "Default")
      (node (ref "U1") (pin "139") (pinfunction "PB8/TIM4_CH3/SDIO_D4_139") (pintype "passive"))
    )
    (net (code "168") (name "unconnected-(U1-PB9{slash}TIM4_CH4{slash}SDIO_D5-Pad140)") (class "Default")
      (node (ref "U1") (pin "140") (pinfunction "PB9/TIM4_CH4/SDIO_D5_140") (pintype "passive"))
    )
    (net (code "169") (name "unconnected-(U1-PC5{slash}ADC12_IN15-Pad45)") (class "Default")
      (node (ref "U1") (pin "45") (pinfunction "PC5/ADC12_IN15_45") (pintype "passive"))
    )
    (net (code "170") (name "unconnected-(U1-PC6{slash}I2S2_MCK{slash}TIM8_CH1{slash}SDIO_D6-Pad96)") (class "Default")
      (node (ref "U1") (pin "96") (pinfunction "PC6/I2S2_MCK/TIM8_CH1/SDIO_D6_96") (pintype "passive"))
    )
    (net (code "171") (name "unconnected-(U1-PC7{slash}I2S3_MCK{slash}TIM8_CH2{slash}SDIO_D7-Pad97)") (class "Default")
      (node (ref "U1") (pin "97") (pinfunction "PC7/I2S3_MCK/TIM8_CH2/SDIO_D7_97") (pintype "passive"))
    )
    (net (code "172") (name "unconnected-(U1-PC13-TAMPER-RTC-Pad7)") (class "Default")
      (node (ref "U1") (pin "7") (pinfunction "PC13-TAMPER-RTC_7") (pintype "passive"))
    )
    (net (code "173") (name "unconnected-(U1-PD3{slash}FSMC_CLK-Pad117)") (class "Default")
      (node (ref "U1") (pin "117") (pinfunction "PD3/FSMC_CLK_117") (pintype "passive"))
    )
    (net (code "174") (name "unconnected-(U1-PD6{slash}FSMC_NWAIT-Pad122)") (class "Default")
      (node (ref "U1") (pin "122") (pinfunction "PD6/FSMC_NWAIT_122") (pintype "passive"))
    )
    (net (code "175") (name "unconnected-(U1-PD7{slash}FSMC_NE1{slash}FSMC_NCE2-Pad123)") (class "Default")
      (node (ref "U1") (pin "123") (pinfunction "PD7/FSMC_NE1/FSMC_NCE2_123") (pintype "passive"))
    )
    (net (code "176") (name "unconnected-(U1-PF7{slash}ADC3_IN5{slash}FSMC_NREG-Pad19)") (class "Default")
      (node (ref "U1") (pin "19") (pinfunction "PF7/ADC3_IN5/FSMC_NREG_19") (pintype "passive"))
    )
    (net (code "177") (name "unconnected-(U1-PF8{slash}ADC3_IN6{slash}FSMC_NIOWR-Pad20)") (class "Default")
      (node (ref "U1") (pin "20") (pinfunction "PF8/ADC3_IN6/FSMC_NIOWR_20") (pintype "passive"))
    )
    (net (code "178") (name "unconnected-(U1-PF9{slash}ADC3_IN7{slash}FSMC_CD-Pad21)") (class "Default")
      (node (ref "U1") (pin "21") (pinfunction "PF9/ADC3_IN7/FSMC_CD_21") (pintype "passive"))
    )
    (net (code "179") (name "unconnected-(U1-PF10{slash}ADC3_IN8{slash}FSMC_INTR-Pad22)") (class "Default")
      (node (ref "U1") (pin "22") (pinfunction "PF10/ADC3_IN8/FSMC_INTR_22") (pintype "passive"))
    )
    (net (code "180") (name "unconnected-(U1-PG9{slash}FSMC_NE2{slash}FSMC_NCE3-Pad124)") (class "Default")
      (node (ref "U1") (pin "124") (pinfunction "PG9/FSMC_NE2/FSMC_NCE3_124") (pintype "passive"))
    )
    (net (code "181") (name "unconnected-(U1-PG11{slash}FSMC_NCE4_2-Pad126)") (class "Default")
      (node (ref "U1") (pin "126") (pinfunction "PG11/FSMC_NCE4_2_126") (pintype "passive"))
    )
    (net (code "182") (name "unconnected-(U1-PG13{slash}FSMC_A24-Pad128)") (class "Default")
      (node (ref "U1") (pin "128") (pinfunction "PG13/FSMC_A24_128") (pintype "passive"))
    )
    (net (code "183") (name "unconnected-(U1-PG15-Pad132)") (class "Default")
      (node (ref "U1") (pin "132") (pinfunction "PG15_132") (pintype "passive"))
    )
    (net (code "184") (name "unconnected-(U5-Vref-Pad5)") (class "Default")
      (node (ref "U5") (pin "5") (pinfunction "Vref_5") (pintype "output"))
    )
    (net (code "185") (name "unconnected-(U7-NC-Pad1)") (class "Default")
      (node (ref "U7") (pin "1") (pinfunction "NC_1") (pintype "passive"))
    )
    (net (code "186") (name "unconnected-(U7-NC-Pad2)") (class "Default")
      (node (ref "U7") (pin "2") (pinfunction "NC_2") (pintype "passive"))
    )
    (net (code "187") (name "unconnected-(U7-NC-Pad4)") (class "Default")
      (node (ref "U7") (pin "4") (pinfunction "NC_4") (pintype "passive"))
    )
    (net (code "188") (name "unconnected-(U7-NC-Pad5)") (class "Default")
      (node (ref "U7") (pin "5") (pinfunction "NC_5") (pintype "passive"))
    )
    (net (code "189") (name "unconnected-(U7-NC-Pad6)") (class "Default")
      (node (ref "U7") (pin "6") (pinfunction "NC_6") (pintype "passive"))
    )
    (net (code "190") (name "unconnected-(U7-NC-Pad7)") (class "Default")
      (node (ref "U7") (pin "7") (pinfunction "NC_7") (pintype "passive"))
    )
    (net (code "191") (name "unconnected-(U7-NC-Pad9)") (class "Default")
      (node (ref "U7") (pin "9") (pinfunction "NC_9") (pintype "passive"))
    )
    (net (code "192") (name "unconnected-(U7-NC-Pad14)") (class "Default")
      (node (ref "U7") (pin "14") (pinfunction "NC_14") (pintype "passive"))
    )
    (net (code "193") (name "unconnected-(U7-NC-Pad15)") (class "Default")
      (node (ref "U7") (pin "15") (pinfunction "NC_15") (pintype "passive"))
    )
    (net (code "194") (name "unconnected-(U7-NC-Pad16)") (class "Default")
      (node (ref "U7") (pin "16") (pinfunction "NC_16") (pintype "passive"))
    )
    (net (code "195") (name "unconnected-(U7-NC-Pad17)") (class "Default")
      (node (ref "U7") (pin "17") (pinfunction "NC_17") (pintype "passive"))
    )
    (net (code "196") (name "unconnected-(U7-RSTN-Pad8)") (class "Default")
      (node (ref "U7") (pin "8") (pinfunction "RSTN_8") (pintype "passive"))
    )
    (net (code "197") (name "unconnected-(U7-SCL{slash}NC-Pad19)") (class "Default")
      (node (ref "U7") (pin "19") (pinfunction "SCL/NC_19") (pintype "passive"))
    )
    (net (code "198") (name "unconnected-(U7-SDA{slash}NC-Pad18)") (class "Default")
      (node (ref "U7") (pin "18") (pinfunction "SDA/NC_18") (pintype "passive"))
    )
    (net (code "199") (name "unconnected-(U14-CTS#-Pad9)") (class "Default")
      (node (ref "U14") (pin "9") (pinfunction "CTS#_9") (pintype "passive"))
    )
    (net (code "200") (name "unconnected-(U14-DCD#-Pad12)") (class "Default")
      (node (ref "U14") (pin "12") (pinfunction "DCD#_12") (pintype "passive"))
    )
    (net (code "201") (name "unconnected-(U14-DSR#-Pad10)") (class "Default")
      (node (ref "U14") (pin "10") (pinfunction "DSR#_10") (pintype "passive"))
    )
    (net (code "202") (name "unconnected-(U14-DTR#-Pad13)") (class "Default")
      (node (ref "U14") (pin "13") (pinfunction "DTR#_13") (pintype "passive"))
    )
    (net (code "203") (name "unconnected-(U14-R232-Pad15)") (class "Default")
      (node (ref "U14") (pin "15") (pinfunction "R232_15") (pintype "passive"))
    )
    (net (code "204") (name "unconnected-(U14-RI#-Pad11)") (class "Default")
      (node (ref "U14") (pin "11") (pinfunction "RI#_11") (pintype "passive"))
    )
    (net (code "205") (name "unconnected-(U14-RTS#-Pad14)") (class "Default")
      (node (ref "U14") (pin "14") (pinfunction "RTS#_14") (pintype "passive"))
    )
    (net (code "206") (name "unconnected-(U19-GPIO2{slash}DCLK-Pad9)") (class "Default")
      (node (ref "U19") (pin "9") (pinfunction "GPIO2/DCLK_9") (pintype "passive+no_connect"))
    )
    (net (code "207") (name "unconnected-(U19-GPIO3{slash}SDATA-Pad10)") (class "Default")
      (node (ref "U19") (pin "10") (pinfunction "GPIO3/SDATA_10") (pintype "passive+no_connect"))
    )
    (net (code "208") (name "unconnected-(U19-GPIO5{slash}I2S_MCLK-Pad25)") (class "Default")
      (node (ref "U19") (pin "25") (pinfunction "GPIO5/I2S_MCLK_25") (pintype "passive+no_connect"))
    )
    (net (code "209") (name "unconnected-(U19-GPIO6{slash}I2S_SCLK-Pad11)") (class "Default")
      (node (ref "U19") (pin "11") (pinfunction "GPIO6/I2S_SCLK_11") (pintype "passive+no_connect"))
    )
    (net (code "210") (name "unconnected-(U19-GPIO7{slash}I2S_SDATA-Pad12)") (class "Default")
      (node (ref "U19") (pin "12") (pinfunction "GPIO7/I2S_SDATA_12") (pintype "passive+no_connect"))
    )
    (net (code "211") (name "unconnected-(U19-TX-Pad27)") (class "Default")
      (node (ref "U19") (pin "27") (pinfunction "TX_27") (pintype "passive+no_connect"))
    )
    (net (code "212") (name "unconnected-(U19-VCO-Pad15)") (class "Default")
      (node (ref "U19") (pin "15") (pinfunction "VCO_15") (pintype "passive+no_connect"))
    )
    (net (code "213") (name "unconnected-(USB_232-NC-Pad4)") (class "Default")
      (node (ref "USB_232") (pin "4") (pinfunction "NC_4") (pintype "passive"))
    )
    (net (code "214") (name "unconnected-(USB_SLAVE-NC-Pad4)") (class "Default")
      (node (ref "USB_SLAVE") (pin "4") (pinfunction "NC_4") (pintype "passive"))
    )
  )
)
